# controller.net
KiCad netlist of a schematic drawn in EAGLE
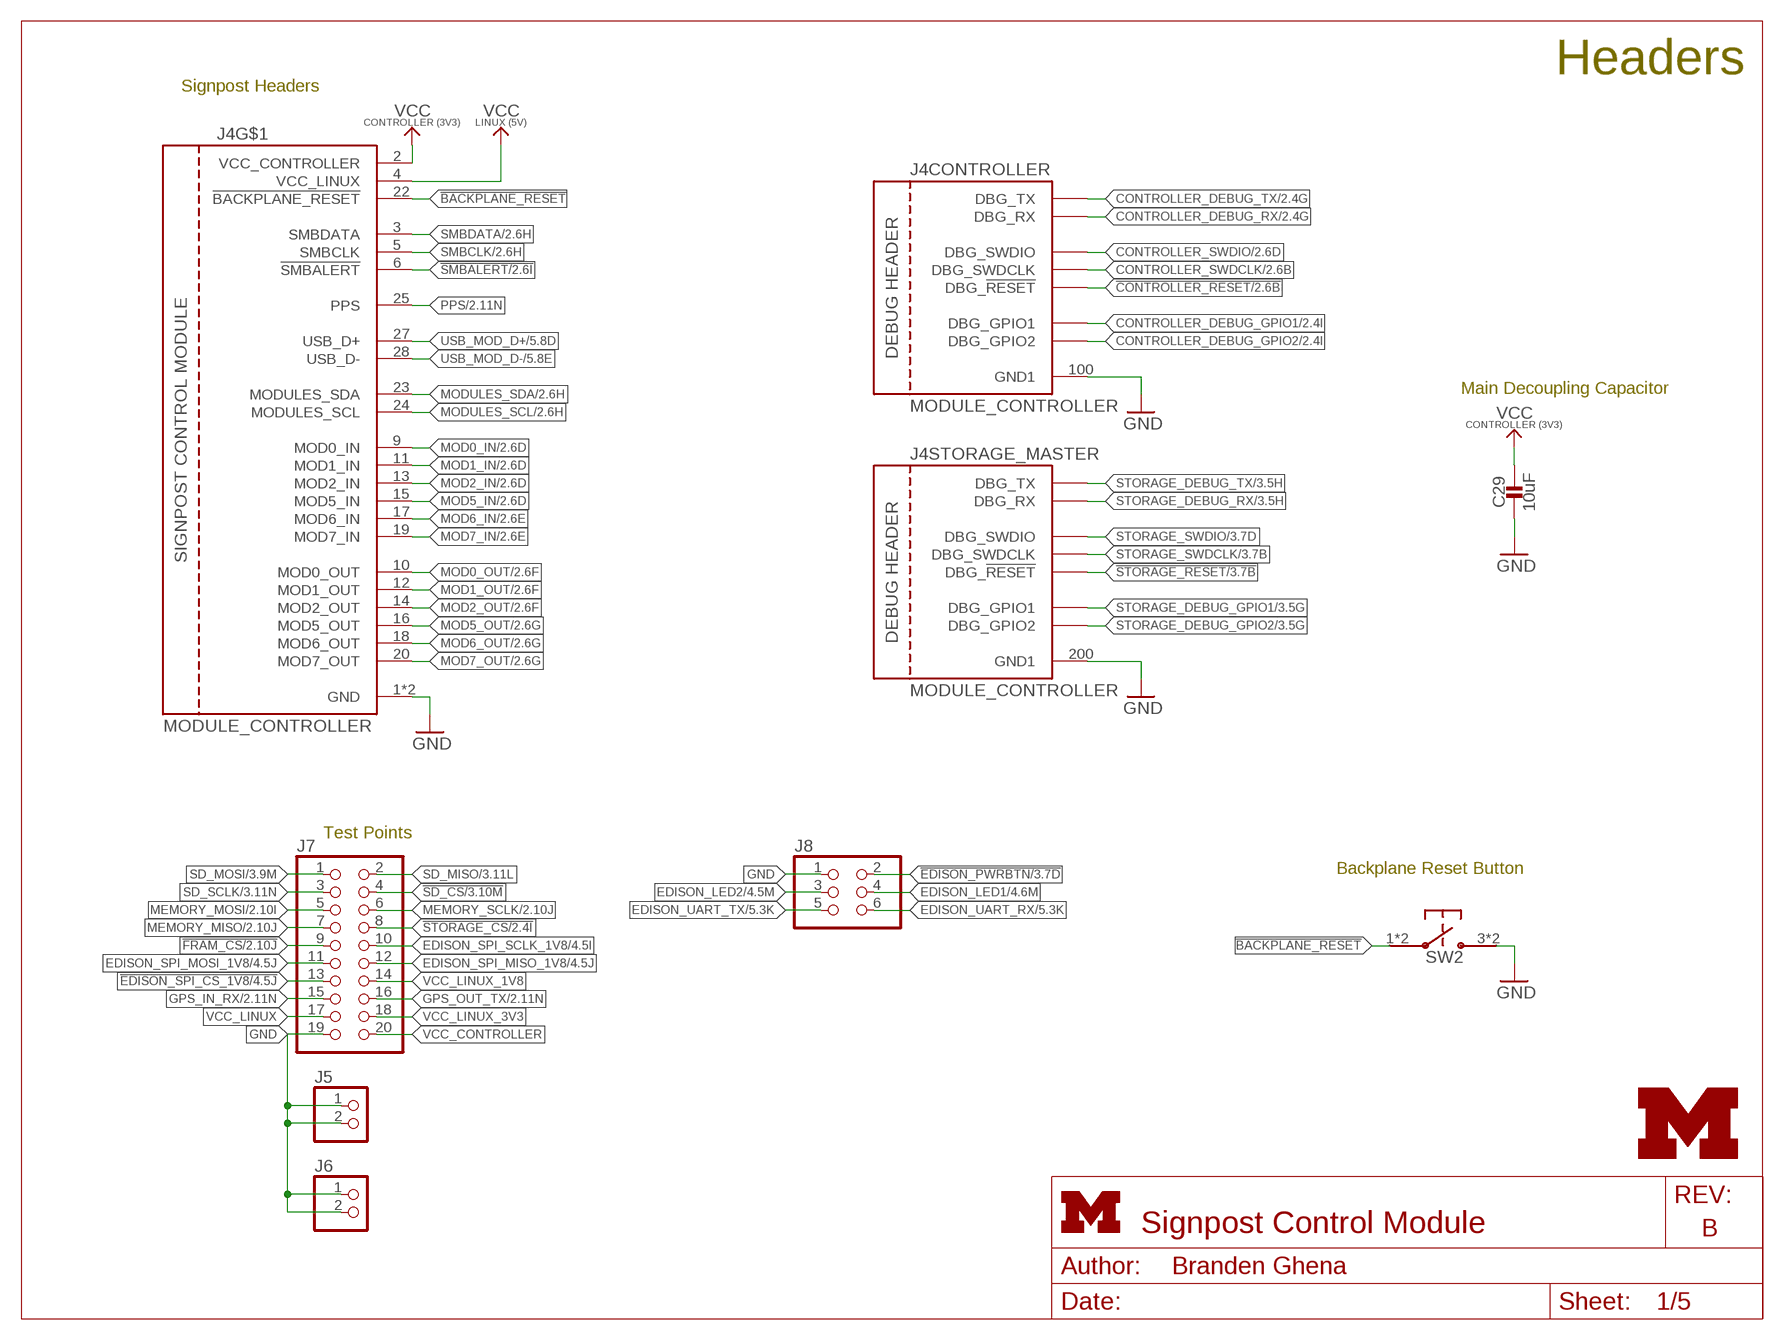
[diagram p0: schematic, sheet 1]
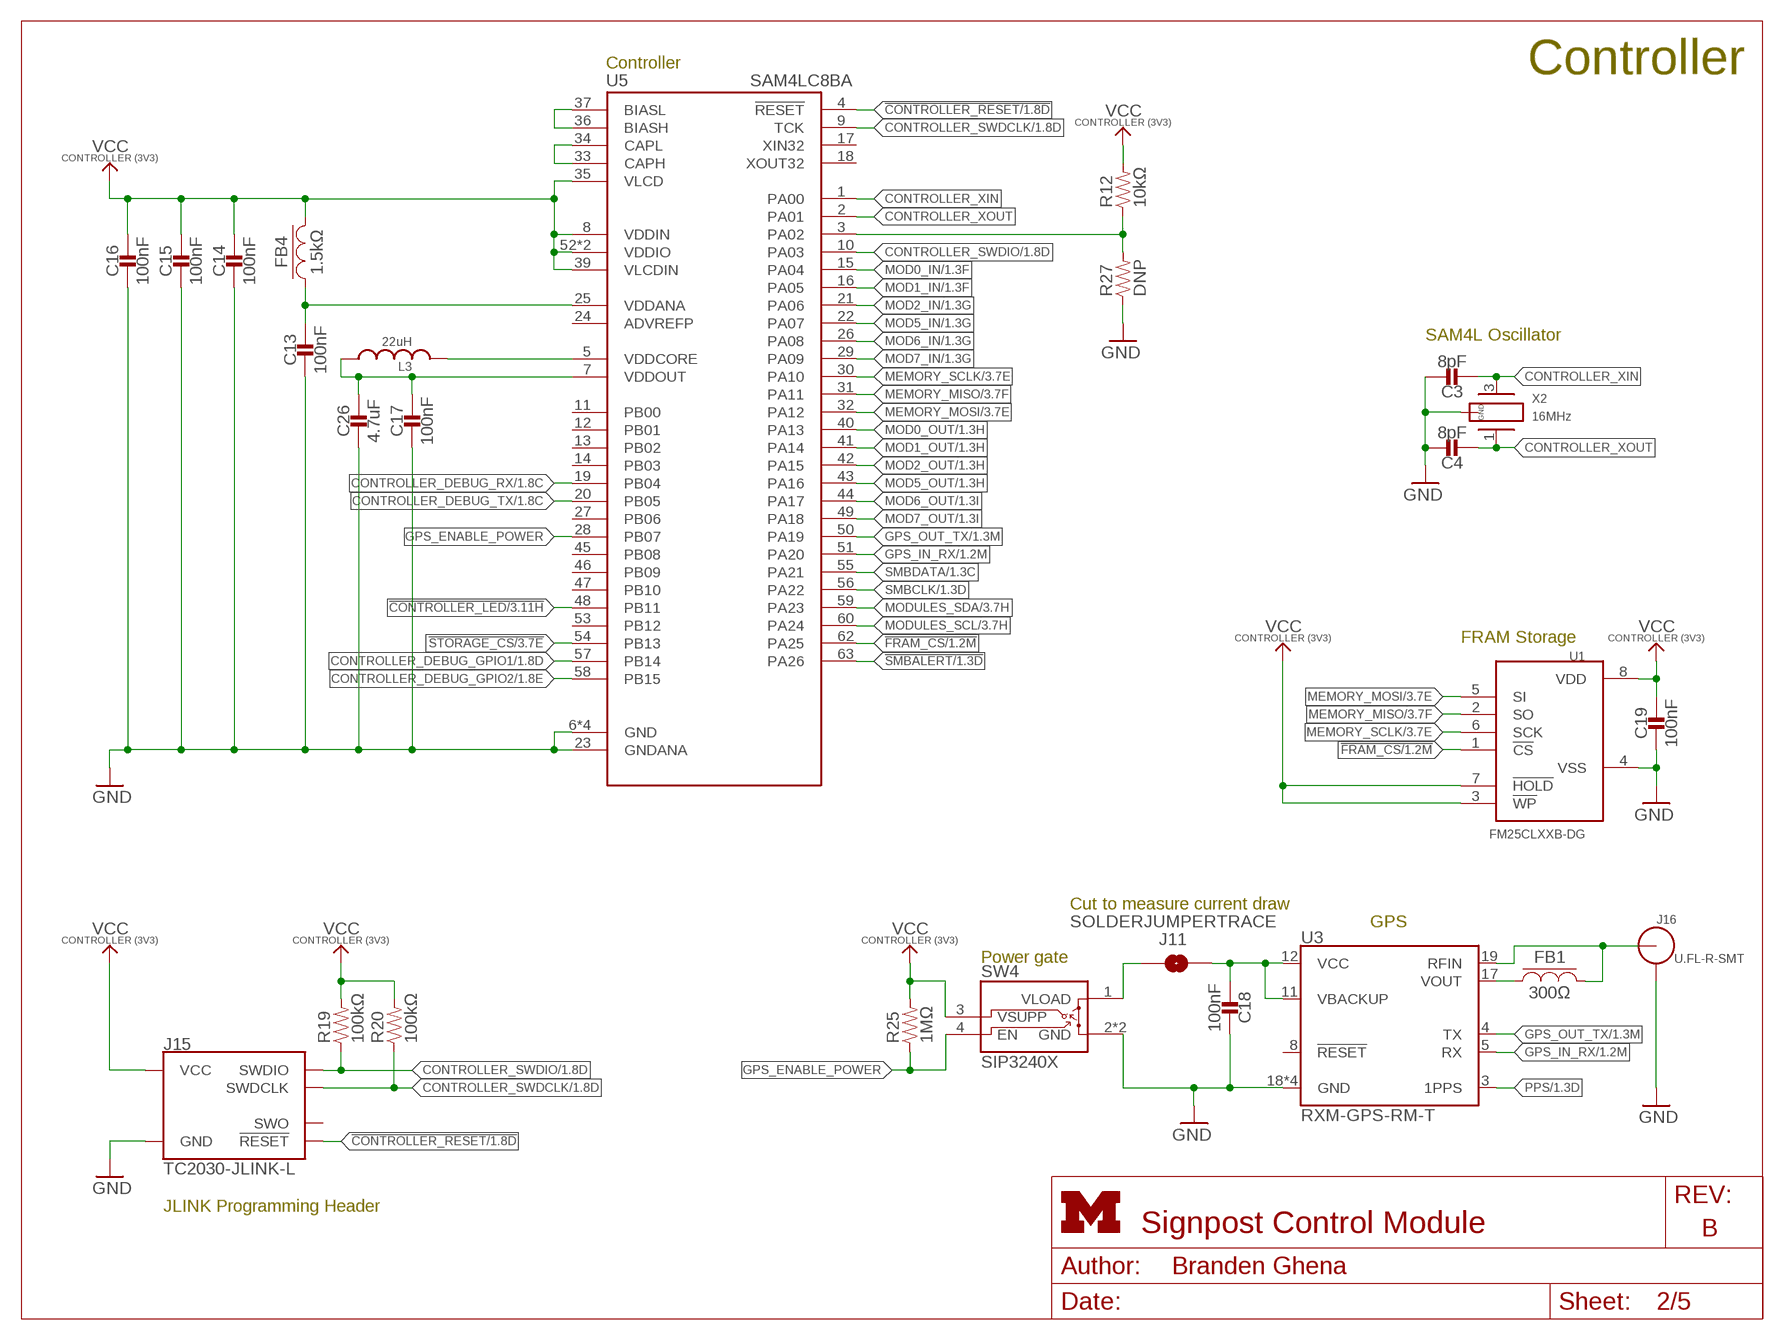
[diagram p1: schematic, sheet 2]
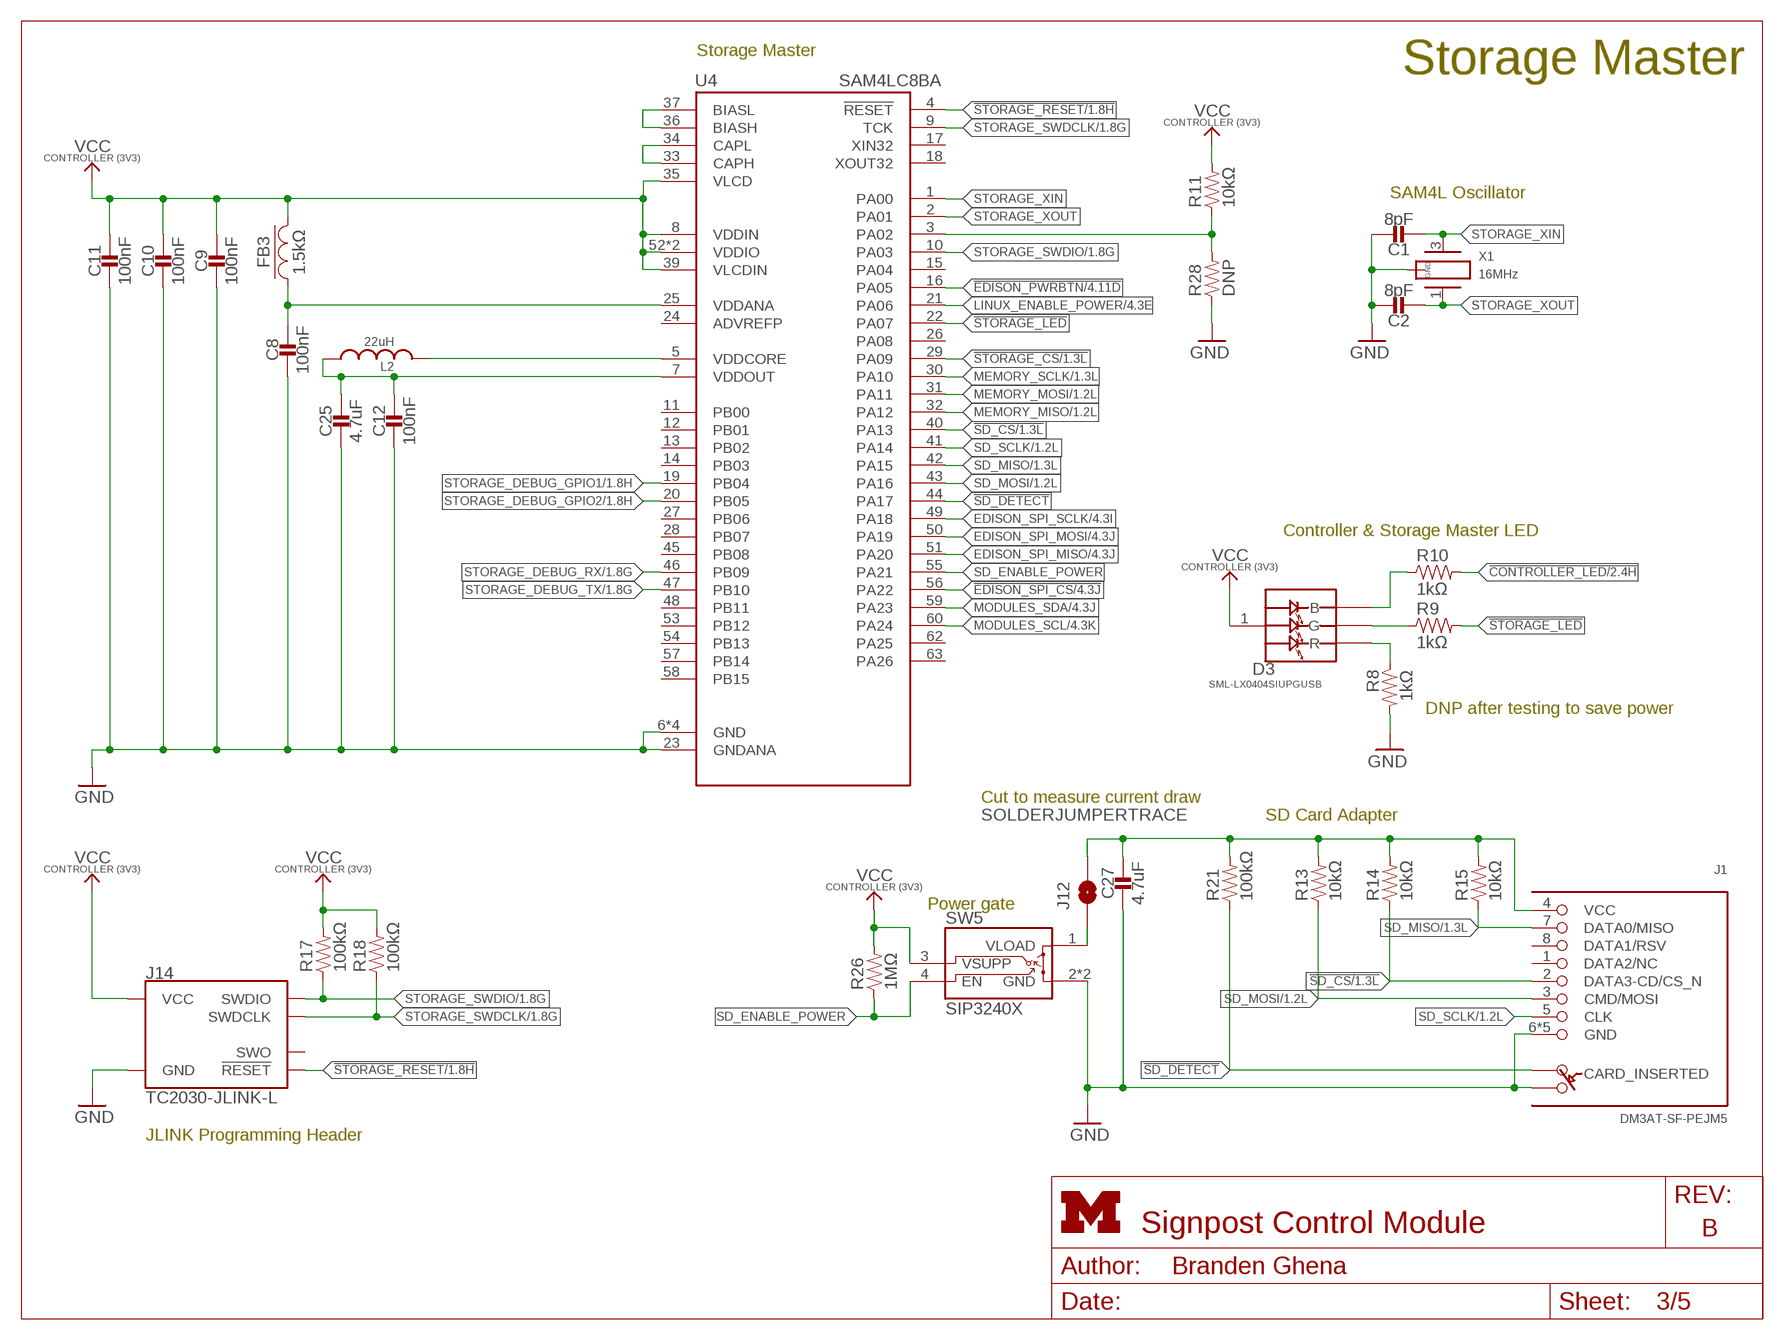
[diagram p2: schematic, sheet 3]
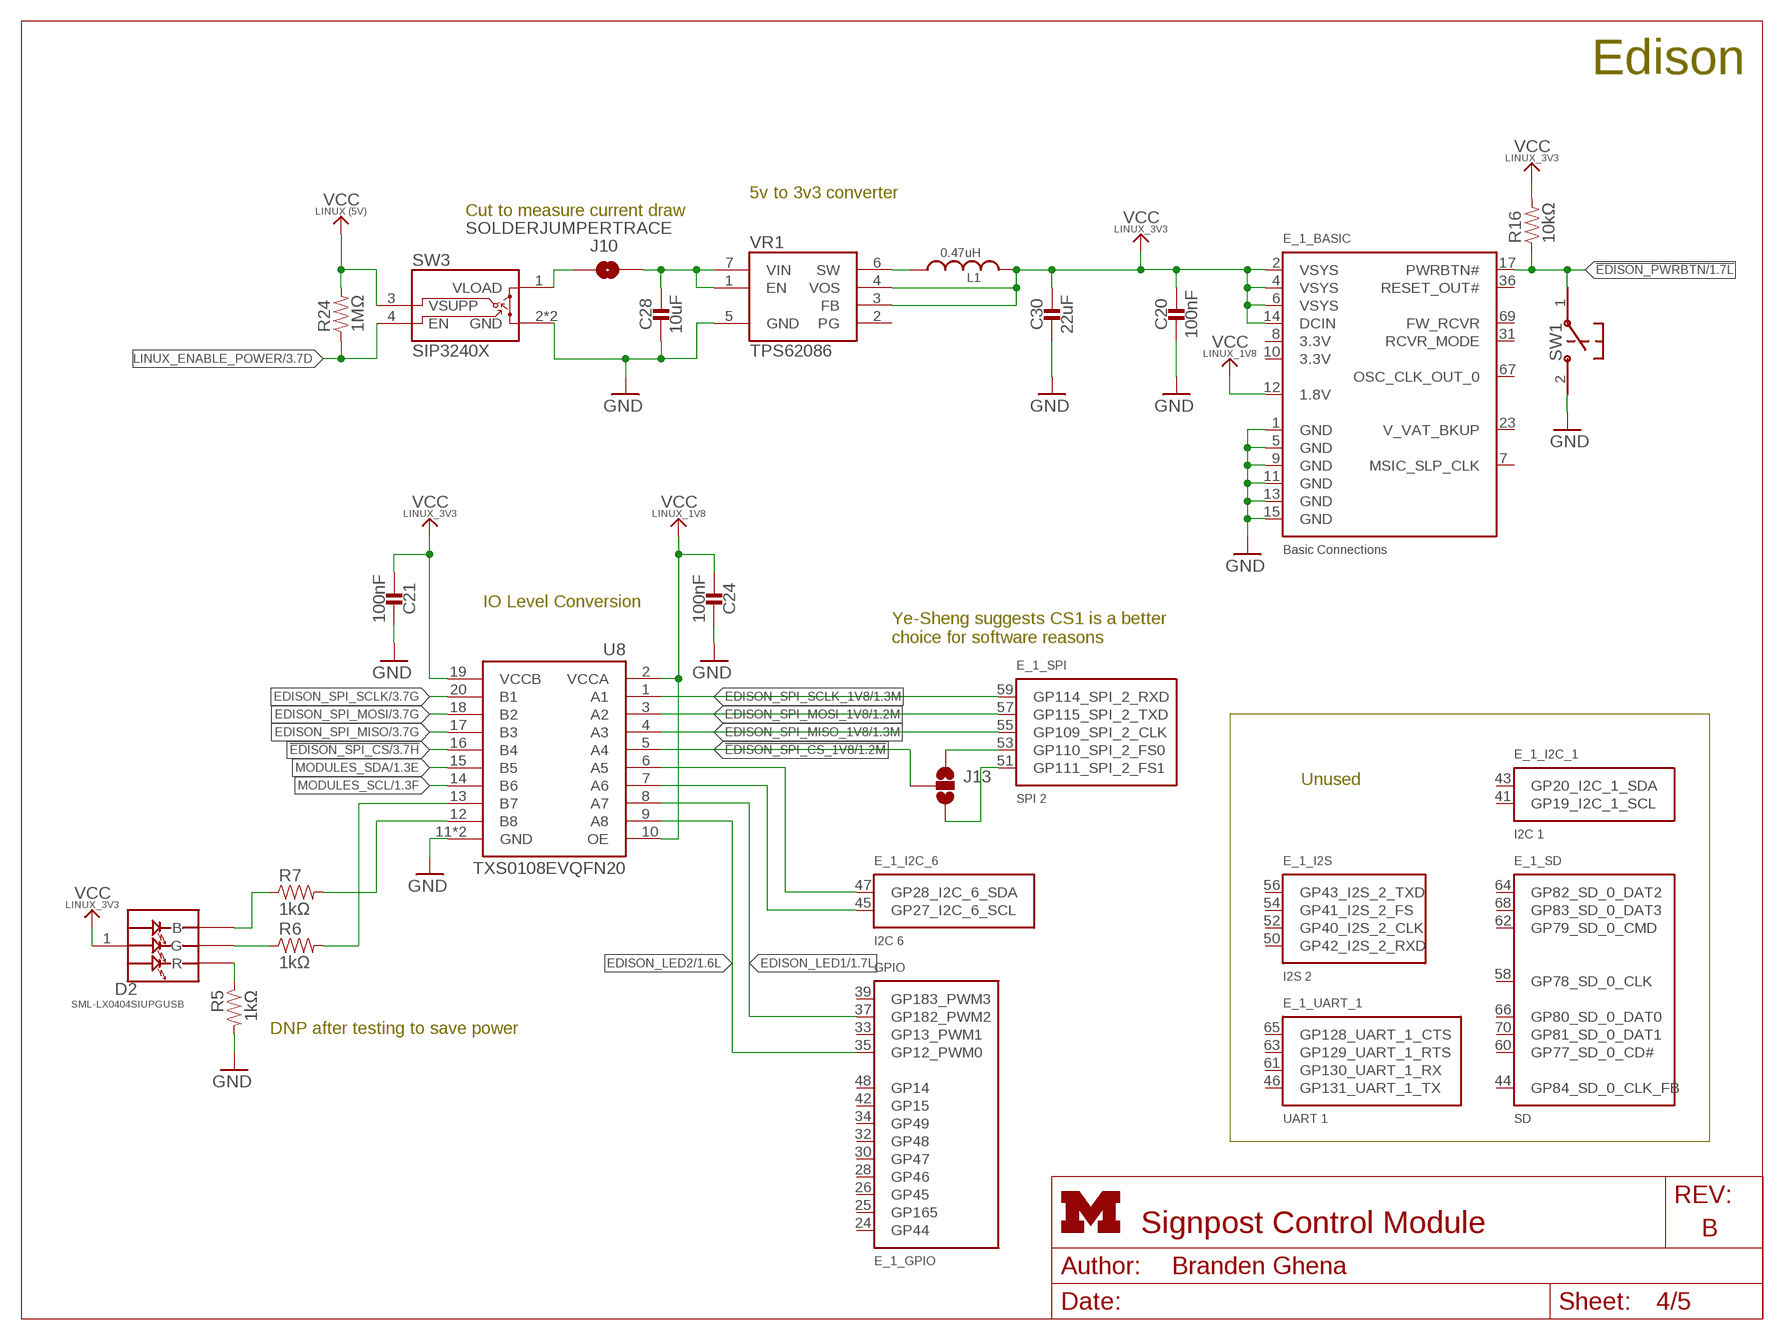
[diagram p3: schematic, sheet 4]
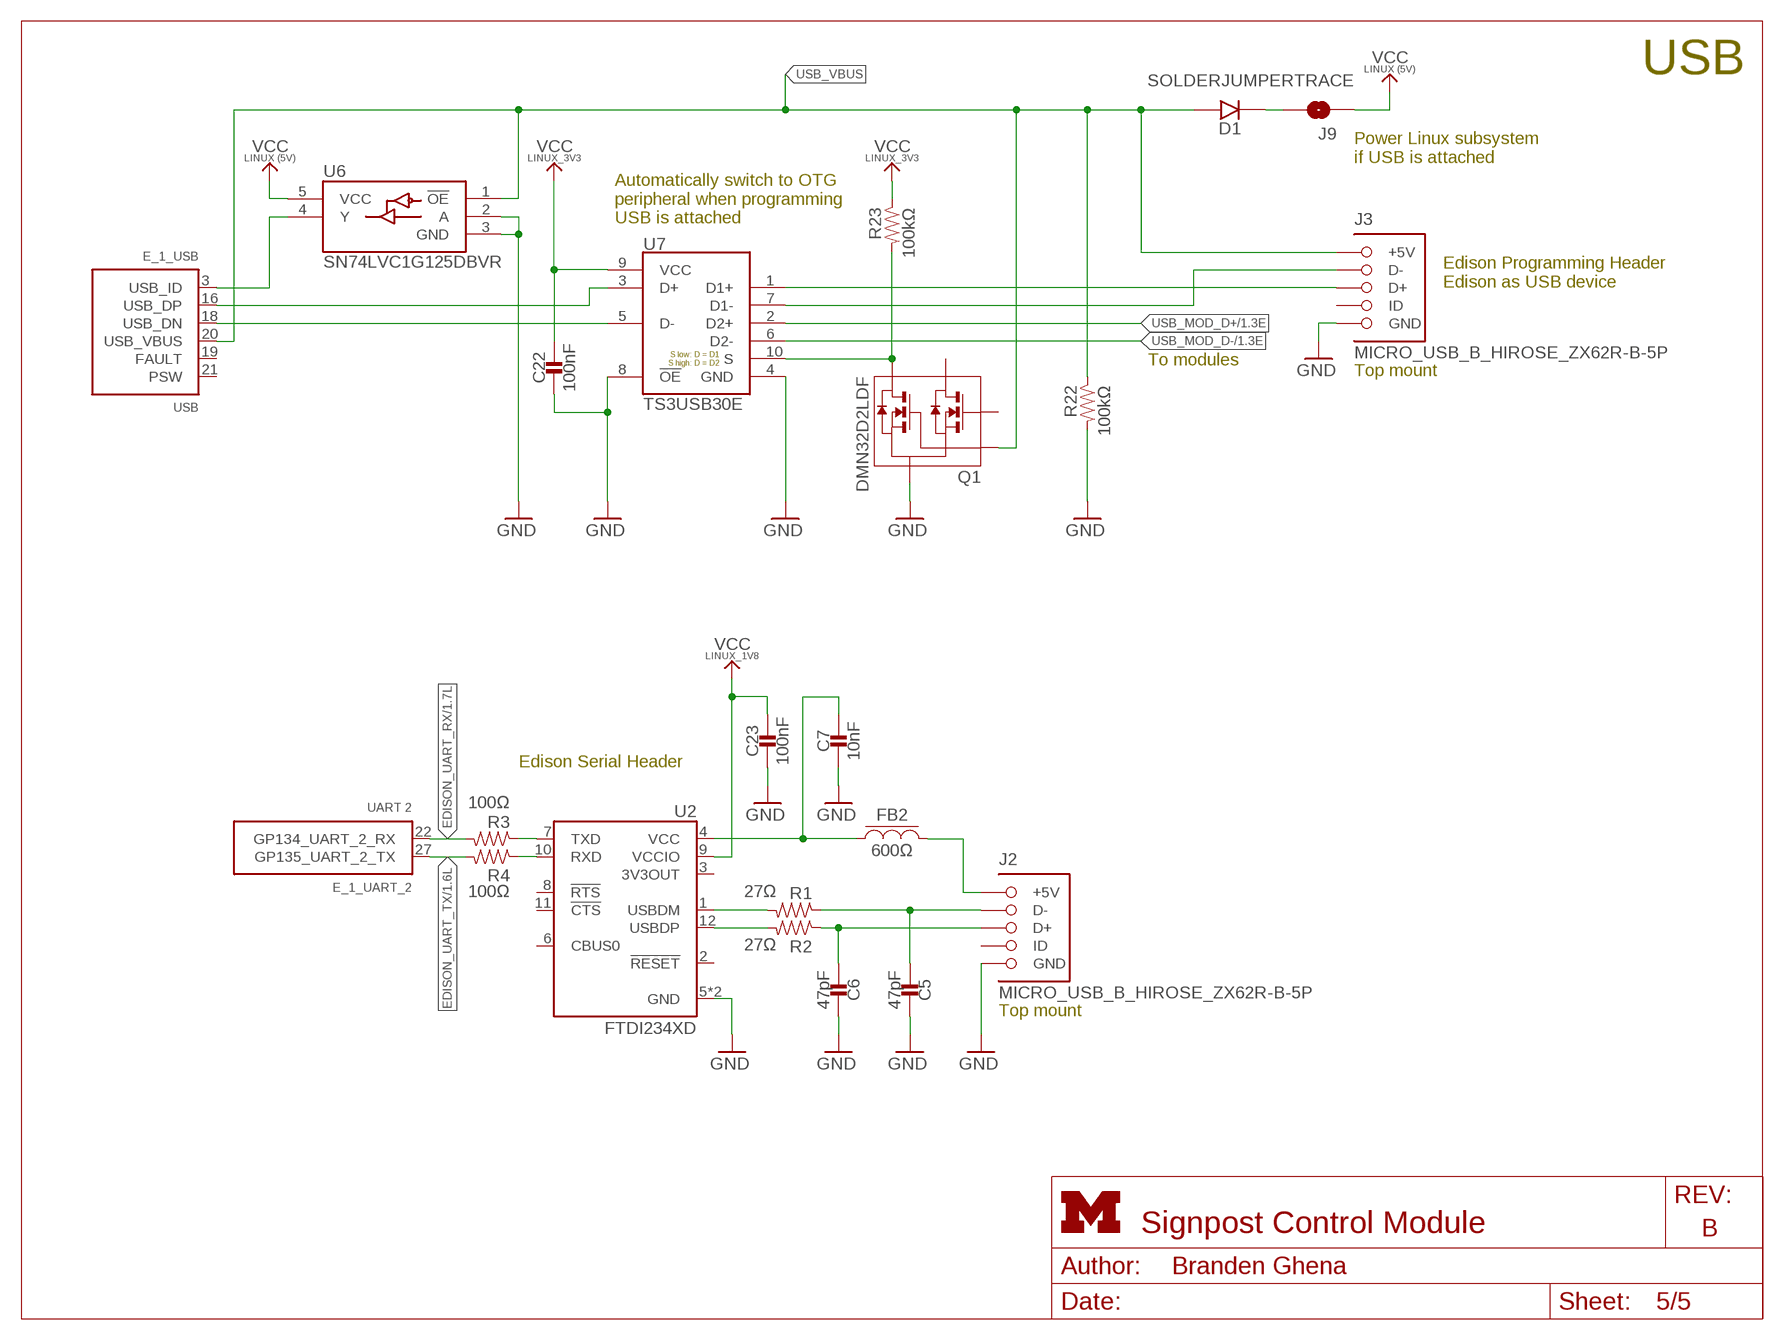
[diagram p4: schematic, sheet 5]

(export (version "E")
  (design (tool "Eeschema 10.0.6"))
  (components
    (comp (ref "C29")
      (value "10uF")
      (footprint "eagle-import:0402_CAP")
      (libsource (lib "eagle-import") (part "CAPACITOR0402_CAP"))
    )
    (comp (ref "J4")
      (value "MODULE_CONTROLLER")
      (footprint "eagle-import:MODULE_CONTROLLER")
      (libsource (lib "eagle-import") (part "MODULE_CONTROLLER"))
    )
    (comp (ref "J5")
      (value "PINHD-1X2")
      (footprint "eagle-import:1X02")
      (libsource (lib "eagle-import") (part "PINHD-1X2"))
    )
    (comp (ref "J6")
      (value "PINHD-1X2")
      (footprint "eagle-import:1X02")
      (libsource (lib "eagle-import") (part "PINHD-1X2"))
    )
    (comp (ref "J7")
      (value "PINHD-2X10")
      (footprint "eagle-import:2X10")
      (libsource (lib "eagle-import") (part "PINHD-2X10"))
    )
    (comp (ref "J8")
      (value "PINHD-2X3")
      (footprint "eagle-import:2X03")
      (libsource (lib "eagle-import") (part "PINHD-2X3"))
    )
    (comp (ref "LOGO1")
      (value "UMICH_SOLID_MEDIUM")
      (footprint "eagle-import:UMICH_SOLID_200MIL")
      (libsource (lib "eagle-import") (part "UMICH_SOLID_MEDIUM"))
    )
    (comp (ref "SW2")
      (value "PTS810SJ")
      (footprint "eagle-import:PTS810SJ")
      (libsource (lib "eagle-import") (part "PTS810SJ"))
    )
    (comp (ref "C1")
      (value "8pF")
      (footprint "eagle-import:0402_CAP")
      (libsource (lib "eagle-import") (part "CAPACITOR0402_CAP"))
    )
    (comp (ref "C2")
      (value "8pF")
      (footprint "eagle-import:0402_CAP")
      (libsource (lib "eagle-import") (part "CAPACITOR0402_CAP"))
    )
    (comp (ref "C8")
      (value "100nF")
      (footprint "eagle-import:0402_CAP")
      (libsource (lib "eagle-import") (part "CAPACITOR0402_CAP"))
    )
    (comp (ref "C9")
      (value "100nF")
      (footprint "eagle-import:0402_CAP")
      (libsource (lib "eagle-import") (part "CAPACITOR0402_CAP"))
    )
    (comp (ref "C10")
      (value "100nF")
      (footprint "eagle-import:0402_CAP")
      (libsource (lib "eagle-import") (part "CAPACITOR0402_CAP"))
    )
    (comp (ref "C11")
      (value "100nF")
      (footprint "eagle-import:0402_CAP")
      (libsource (lib "eagle-import") (part "CAPACITOR0402_CAP"))
    )
    (comp (ref "C12")
      (value "100nF")
      (footprint "eagle-import:0402_CAP")
      (libsource (lib "eagle-import") (part "CAPACITOR0402_CAP"))
    )
    (comp (ref "C25")
      (value "4.7uF")
      (footprint "eagle-import:0402_CAP")
      (libsource (lib "eagle-import") (part "CAPACITOR0402_CAP"))
    )
    (comp (ref "C27")
      (value "4.7uF")
      (footprint "eagle-import:0402_CAP")
      (libsource (lib "eagle-import") (part "CAPACITOR0402_CAP"))
    )
    (comp (ref "D3")
      (value "SML-LX0404SIUPGUSB")
      (footprint "eagle-import:1MM_SQ_4PAD")
      (libsource (lib "eagle-import") (part "SML-LX0404SIUPGUSB"))
    )
    (comp (ref "FB3")
      (value "1.5kΩ")
      (footprint "eagle-import:0402_CAP")
      (libsource (lib "eagle-import") (part "FERRITE_BEAD0402"))
    )
    (comp (ref "J1")
      (value "DM3AT-SF-PEJM5")
      (footprint "eagle-import:DM3AT-SF-PEJM5")
      (libsource (lib "eagle-import") (part "DM3AT-SF-PEJM5"))
    )
    (comp (ref "J12")
      (value "SOLDERJUMPERTRACE")
      (footprint "eagle-import:SJ_2S-TRACE")
      (libsource (lib "eagle-import") (part "SOLDERJUMPERTRACE"))
    )
    (comp (ref "J14")
      (value "TC2030-JLINK-L")
      (footprint "eagle-import:TC2030-IDC")
      (libsource (lib "eagle-import") (part "TC2030-JLINK-L"))
    )
    (comp (ref "L2")
      (value "22uH")
      (footprint "eagle-import:1212")
      (libsource (lib "eagle-import") (part "LHQ3NP"))
    )
    (comp (ref "R8")
      (value "1kΩ")
      (footprint "eagle-import:0402_RES")
      (libsource (lib "eagle-import") (part "RESISTOR0402_RES"))
    )
    (comp (ref "R9")
      (value "1kΩ")
      (footprint "eagle-import:0402_RES")
      (libsource (lib "eagle-import") (part "RESISTOR0402_RES"))
    )
    (comp (ref "R10")
      (value "1kΩ")
      (footprint "eagle-import:0402_RES")
      (libsource (lib "eagle-import") (part "RESISTOR0402_RES"))
    )
    (comp (ref "R11")
      (value "10kΩ")
      (footprint "eagle-import:0402_RES")
      (libsource (lib "eagle-import") (part "RESISTOR0402_RES"))
    )
    (comp (ref "R13")
      (value "10kΩ")
      (footprint "eagle-import:0402_RES")
      (libsource (lib "eagle-import") (part "RESISTOR0402_RES"))
    )
    (comp (ref "R14")
      (value "10kΩ")
      (footprint "eagle-import:0402_RES")
      (libsource (lib "eagle-import") (part "RESISTOR0402_RES"))
    )
    (comp (ref "R15")
      (value "10kΩ")
      (footprint "eagle-import:0402_RES")
      (libsource (lib "eagle-import") (part "RESISTOR0402_RES"))
    )
    (comp (ref "R17")
      (value "100kΩ")
      (footprint "eagle-import:0402_RES")
      (libsource (lib "eagle-import") (part "RESISTOR0402_RES"))
    )
    (comp (ref "R18")
      (value "100kΩ")
      (footprint "eagle-import:0402_RES")
      (libsource (lib "eagle-import") (part "RESISTOR0402_RES"))
    )
    (comp (ref "R21")
      (value "100kΩ")
      (footprint "eagle-import:0402_RES")
      (libsource (lib "eagle-import") (part "RESISTOR0402_RES"))
    )
    (comp (ref "R26")
      (value "1MΩ")
      (footprint "eagle-import:0402_RES")
      (libsource (lib "eagle-import") (part "RESISTOR0402_RES"))
    )
    (comp (ref "R28")
      (value "DNP")
      (footprint "eagle-import:0402_RES")
      (libsource (lib "eagle-import") (part "RESISTOR0402_RES"))
    )
    (comp (ref "SW5")
      (value "SIP3240X")
      (footprint "eagle-import:TDFN4")
      (libsource (lib "eagle-import") (part "SIP3240X"))
    )
    (comp (ref "U4")
      (value "SAM4LC8BA")
      (footprint "eagle-import:QFN-64-9MM")
      (libsource (lib "eagle-import") (part "SAM4LC8BA"))
    )
    (comp (ref "X1")
      (value "16MHz")
      (footprint "eagle-import:FHXXX")
      (libsource (lib "eagle-import") (part "FH1600015"))
    )
    (comp (ref "C20")
      (value "100nF")
      (footprint "eagle-import:0402_CAP")
      (libsource (lib "eagle-import") (part "CAPACITOR0402_CAP"))
    )
    (comp (ref "C21")
      (value "100nF")
      (footprint "eagle-import:0402_CAP")
      (libsource (lib "eagle-import") (part "CAPACITOR0402_CAP"))
    )
    (comp (ref "C24")
      (value "100nF")
      (footprint "eagle-import:0402_CAP")
      (libsource (lib "eagle-import") (part "CAPACITOR0402_CAP"))
    )
    (comp (ref "C28")
      (value "10uF")
      (footprint "eagle-import:0805_CAP")
      (libsource (lib "eagle-import") (part "CAPACITOR0805_CAP"))
    )
    (comp (ref "C30")
      (value "22uF")
      (footprint "eagle-import:0805_CAP")
      (libsource (lib "eagle-import") (part "CAPACITOR0805_CAP"))
    )
    (comp (ref "D2")
      (value "SML-LX0404SIUPGUSB")
      (footprint "eagle-import:1MM_SQ_4PAD")
      (libsource (lib "eagle-import") (part "SML-LX0404SIUPGUSB"))
    )
    (comp (ref "E_1")
      (value "EDISON_CONNECTOR_SEGMENTED")
      (footprint "eagle-import:EDISON_DAUGHTER")
      (fields (field (name "MOUSER") "798-DF40HC3070DS4V51") (field (name "AMAZON") "B00PTVSS4A"))
      (libsource (lib "eagle-import") (part "EDISON_CONNECTOR_SEGMENTED"))
    )
    (comp (ref "J10")
      (value "SOLDERJUMPERTRACE")
      (footprint "eagle-import:SJ_2S-TRACE")
      (libsource (lib "eagle-import") (part "SOLDERJUMPERTRACE"))
    )
    (comp (ref "J13")
      (value "SOLDERJUMPER_2WAYPASTE2&3")
      (footprint "eagle-import:SJ_3_PASTE2&3")
      (libsource (lib "eagle-import") (part "SOLDERJUMPER_2WAYPASTE2&3"))
    )
    (comp (ref "L1")
      (value "0.47uH")
      (footprint "eagle-import:DFE322512C")
      (libsource (lib "eagle-import") (part "INDUCTORDFE322512C"))
    )
    (comp (ref "R5")
      (value "1kΩ")
      (footprint "eagle-import:0402_RES")
      (libsource (lib "eagle-import") (part "RESISTOR0402_RES"))
    )
    (comp (ref "R6")
      (value "1kΩ")
      (footprint "eagle-import:0402_RES")
      (libsource (lib "eagle-import") (part "RESISTOR0402_RES"))
    )
    (comp (ref "R7")
      (value "1kΩ")
      (footprint "eagle-import:0402_RES")
      (libsource (lib "eagle-import") (part "RESISTOR0402_RES"))
    )
    (comp (ref "R16")
      (value "10kΩ")
      (footprint "eagle-import:0402_RES")
      (libsource (lib "eagle-import") (part "RESISTOR0402_RES"))
    )
    (comp (ref "R24")
      (value "1MΩ")
      (footprint "eagle-import:0402_RES")
      (libsource (lib "eagle-import") (part "RESISTOR0402_RES"))
    )
    (comp (ref "SW1")
      (value "B3U-1000P")
      (footprint "eagle-import:B3U-1000P")
      (libsource (lib "eagle-import") (part "B3U-1000P"))
    )
    (comp (ref "SW3")
      (value "SIP3240X")
      (footprint "eagle-import:TDFN4")
      (libsource (lib "eagle-import") (part "SIP3240X"))
    )
    (comp (ref "U8")
      (value "TXS0108EVQFN20")
      (footprint "eagle-import:R-PVQFN-N20")
      (libsource (lib "eagle-import") (part "TXS0108EVQFN20"))
    )
    (comp (ref "VR1")
      (value "TPS62086")
      (footprint "eagle-import:RLT0007A")
      (libsource (lib "eagle-import") (part "TPS62086"))
    )
    (comp (ref "C3")
      (value "8pF")
      (footprint "eagle-import:0402_CAP")
      (libsource (lib "eagle-import") (part "CAPACITOR0402_CAP"))
    )
    (comp (ref "C4")
      (value "8pF")
      (footprint "eagle-import:0402_CAP")
      (libsource (lib "eagle-import") (part "CAPACITOR0402_CAP"))
    )
    (comp (ref "C13")
      (value "100nF")
      (footprint "eagle-import:0402_CAP")
      (libsource (lib "eagle-import") (part "CAPACITOR0402_CAP"))
    )
    (comp (ref "C14")
      (value "100nF")
      (footprint "eagle-import:0402_CAP")
      (libsource (lib "eagle-import") (part "CAPACITOR0402_CAP"))
    )
    (comp (ref "C15")
      (value "100nF")
      (footprint "eagle-import:0402_CAP")
      (libsource (lib "eagle-import") (part "CAPACITOR0402_CAP"))
    )
    (comp (ref "C16")
      (value "100nF")
      (footprint "eagle-import:0402_CAP")
      (libsource (lib "eagle-import") (part "CAPACITOR0402_CAP"))
    )
    (comp (ref "C17")
      (value "100nF")
      (footprint "eagle-import:0402_CAP")
      (libsource (lib "eagle-import") (part "CAPACITOR0402_CAP"))
    )
    (comp (ref "C18")
      (value "100nF")
      (footprint "eagle-import:0402_CAP")
      (libsource (lib "eagle-import") (part "CAPACITOR0402_CAP"))
    )
    (comp (ref "C19")
      (value "100nF")
      (footprint "eagle-import:0402_CAP")
      (libsource (lib "eagle-import") (part "CAPACITOR0402_CAP"))
    )
    (comp (ref "C26")
      (value "4.7uF")
      (footprint "eagle-import:0402_CAP")
      (libsource (lib "eagle-import") (part "CAPACITOR0402_CAP"))
    )
    (comp (ref "FB1")
      (value "300Ω")
      (footprint "eagle-import:0402_CAP")
      (libsource (lib "eagle-import") (part "FERRITE_BEAD0402"))
    )
    (comp (ref "FB4")
      (value "1.5kΩ")
      (footprint "eagle-import:0402_CAP")
      (libsource (lib "eagle-import") (part "FERRITE_BEAD0402"))
    )
    (comp (ref "J11")
      (value "SOLDERJUMPERTRACE")
      (footprint "eagle-import:SJ_2S-TRACE")
      (libsource (lib "eagle-import") (part "SOLDERJUMPERTRACE"))
    )
    (comp (ref "J15")
      (value "TC2030-JLINK-L")
      (footprint "eagle-import:TC2030-IDC")
      (libsource (lib "eagle-import") (part "TC2030-JLINK-L"))
    )
    (comp (ref "J16")
      (value "U.FL-R-SMT")
      (footprint "eagle-import:U.FL_SMT")
      (libsource (lib "eagle-import") (part "U.FL-R-SMT"))
    )
    (comp (ref "L3")
      (value "22uH")
      (footprint "eagle-import:1212")
      (libsource (lib "eagle-import") (part "LHQ3NP"))
    )
    (comp (ref "R12")
      (value "10kΩ")
      (footprint "eagle-import:0402_RES")
      (libsource (lib "eagle-import") (part "RESISTOR0402_RES"))
    )
    (comp (ref "R19")
      (value "100kΩ")
      (footprint "eagle-import:0402_RES")
      (libsource (lib "eagle-import") (part "RESISTOR0402_RES"))
    )
    (comp (ref "R20")
      (value "100kΩ")
      (footprint "eagle-import:0402_RES")
      (libsource (lib "eagle-import") (part "RESISTOR0402_RES"))
    )
    (comp (ref "R25")
      (value "1MΩ")
      (footprint "eagle-import:0402_RES")
      (libsource (lib "eagle-import") (part "RESISTOR0402_RES"))
    )
    (comp (ref "R27")
      (value "DNP")
      (footprint "eagle-import:0402_RES")
      (libsource (lib "eagle-import") (part "RESISTOR0402_RES"))
    )
    (comp (ref "SW4")
      (value "SIP3240X")
      (footprint "eagle-import:TDFN4")
      (libsource (lib "eagle-import") (part "SIP3240X"))
    )
    (comp (ref "U1")
      (value "FM25CLXXB-DG")
      (footprint "eagle-import:TDFN-8")
      (libsource (lib "eagle-import") (part "FM25CLXXB-DG"))
    )
    (comp (ref "U3")
      (value "RXM-GPS-RM-T")
      (footprint "eagle-import:RXM-GPS-RM-T")
      (libsource (lib "eagle-import") (part "RXM-GPS-RM-T"))
    )
    (comp (ref "U5")
      (value "SAM4LC8BA")
      (footprint "eagle-import:QFN-64-9MM")
      (libsource (lib "eagle-import") (part "SAM4LC8BA"))
    )
    (comp (ref "X2")
      (value "16MHz")
      (footprint "eagle-import:FHXXX")
      (libsource (lib "eagle-import") (part "FH1600015"))
    )
    (comp (ref "C5")
      (value "47pF")
      (footprint "eagle-import:0402_CAP")
      (libsource (lib "eagle-import") (part "CAPACITOR0402_CAP"))
    )
    (comp (ref "C6")
      (value "47pF")
      (footprint "eagle-import:0402_CAP")
      (libsource (lib "eagle-import") (part "CAPACITOR0402_CAP"))
    )
    (comp (ref "C7")
      (value "10nF")
      (footprint "eagle-import:0402_CAP")
      (libsource (lib "eagle-import") (part "CAPACITOR0402_CAP"))
    )
    (comp (ref "C22")
      (value "100nF")
      (footprint "eagle-import:0402_CAP")
      (libsource (lib "eagle-import") (part "CAPACITOR0402_CAP"))
    )
    (comp (ref "C23")
      (value "100nF")
      (footprint "eagle-import:0402_CAP")
      (libsource (lib "eagle-import") (part "CAPACITOR0402_CAP"))
    )
    (comp (ref "D1")
      (value "DIODE")
      (footprint "eagle-import:0805_DIODE")
      (libsource (lib "eagle-import") (part "DIODE"))
    )
    (comp (ref "FB2")
      (value "600Ω")
      (footprint "eagle-import:0805_CAP")
      (libsource (lib "eagle-import") (part "FERRITE_BEAD0805"))
    )
    (comp (ref "J2")
      (value "MICRO_USB_B_HIROSE_ZX62R-B-5P")
      (footprint "eagle-import:USB_MICRO_B-HIROSE-ZX62R-B-5P")
      (fields (field (name "DIGIKEY") "H125274CT-ND"))
      (libsource (lib "eagle-import") (part "MICRO_USB_B_HIROSE_ZX62R-B-5P"))
    )
    (comp (ref "J3")
      (value "MICRO_USB_B_HIROSE_ZX62R-B-5P")
      (footprint "eagle-import:USB_MICRO_B-HIROSE-ZX62R-B-5P")
      (fields (field (name "DIGIKEY") "H125274CT-ND"))
      (libsource (lib "eagle-import") (part "MICRO_USB_B_HIROSE_ZX62R-B-5P"))
    )
    (comp (ref "J9")
      (value "SOLDERJUMPERTRACE")
      (footprint "eagle-import:SJ_2S-TRACE")
      (libsource (lib "eagle-import") (part "SOLDERJUMPERTRACE"))
    )
    (comp (ref "Q1")
      (value "DMN32D2LDF")
      (footprint "eagle-import:SOT353")
      (libsource (lib "eagle-import") (part "DMN32D2LDF"))
    )
    (comp (ref "R1")
      (value "27Ω")
      (footprint "eagle-import:0402_RES")
      (libsource (lib "eagle-import") (part "RESISTOR0402_RES"))
    )
    (comp (ref "R2")
      (value "27Ω")
      (footprint "eagle-import:0402_RES")
      (libsource (lib "eagle-import") (part "RESISTOR0402_RES"))
    )
    (comp (ref "R3")
      (value "100Ω")
      (footprint "eagle-import:0402_RES")
      (libsource (lib "eagle-import") (part "RESISTOR0402_RES"))
    )
    (comp (ref "R4")
      (value "100Ω")
      (footprint "eagle-import:0402_RES")
      (libsource (lib "eagle-import") (part "RESISTOR0402_RES"))
    )
    (comp (ref "R22")
      (value "100kΩ")
      (footprint "eagle-import:0402_RES")
      (libsource (lib "eagle-import") (part "RESISTOR0402_RES"))
    )
    (comp (ref "R23")
      (value "100kΩ")
      (footprint "eagle-import:0402_RES")
      (libsource (lib "eagle-import") (part "RESISTOR0402_RES"))
    )
    (comp (ref "U2")
      (value "FTDI234XD")
      (footprint "eagle-import:DFN-12_3MM")
      (libsource (lib "eagle-import") (part "FTDI234XD"))
    )
    (comp (ref "U6")
      (value "SN74LVC1G125DBVR")
      (footprint "eagle-import:SOT-23-5")
      (libsource (lib "eagle-import") (part "SN74LVC1G125DBVR"))
    )
    (comp (ref "U7")
      (value "TS3USB30E")
      (footprint "eagle-import:UQFN-10")
      (libsource (lib "eagle-import") (part "TS3USB30E"))
    )
  )
  (nets
    (net (code "1") (name "CONTROLLER_DEBUG_GPIO1") (class "Default")
      (node (ref "J4") (pin "101") (pinfunction "DBG_GPIO1_101") (pintype "bidirectional"))
      (node (ref "U5") (pin "57") (pinfunction "PB14_57") (pintype "bidirectional"))
    )
    (net (code "2") (name "CONTROLLER_DEBUG_GPIO2") (class "Default")
      (node (ref "J4") (pin "104") (pinfunction "DBG_GPIO2_104") (pintype "bidirectional"))
      (node (ref "U5") (pin "58") (pinfunction "PB15_58") (pintype "bidirectional"))
    )
    (net (code "3") (name "CONTROLLER_DEBUG_RX") (class "Default")
      (node (ref "J4") (pin "103") (pinfunction "DBG_RX_103") (pintype "bidirectional"))
      (node (ref "U5") (pin "19") (pinfunction "PB04_19") (pintype "bidirectional"))
    )
    (net (code "4") (name "CONTROLLER_DEBUG_TX") (class "Default")
      (node (ref "J4") (pin "102") (pinfunction "DBG_TX_102") (pintype "bidirectional"))
      (node (ref "U5") (pin "20") (pinfunction "PB05_20") (pintype "bidirectional"))
    )
    (net (code "5") (name "CONTROLLER_SWDCLK") (class "Default")
      (node (ref "J15") (pin "4") (pinfunction "SWDCLK_4") (pintype "bidirectional"))
      (node (ref "J4") (pin "106") (pinfunction "DBG_SWDCLK_106") (pintype "bidirectional"))
      (node (ref "R20") (pin "1") (pinfunction "1_1") (pintype "passive"))
      (node (ref "U5") (pin "9") (pinfunction "TCK_9") (pintype "bidirectional"))
    )
    (net (code "6") (name "CONTROLLER_SWDIO") (class "Default")
      (node (ref "J15") (pin "2") (pinfunction "SWDIO_2") (pintype "bidirectional"))
      (node (ref "J4") (pin "107") (pinfunction "DBG_SWDIO_107") (pintype "bidirectional"))
      (node (ref "R19") (pin "1") (pinfunction "1_1") (pintype "passive"))
      (node (ref "U5") (pin "10") (pinfunction "PA03_10") (pintype "bidirectional"))
    )
    (net (code "7") (name "CONTROLLER_XIN") (class "Default")
      (node (ref "C3") (pin "1") (pinfunction "1_1") (pintype "bidirectional"))
      (node (ref "U5") (pin "1") (pinfunction "PA00_1") (pintype "bidirectional"))
      (node (ref "X2") (pin "3") (pinfunction "2_3") (pintype "bidirectional"))
    )
    (net (code "8") (name "CONTROLLER_XOUT") (class "Default")
      (node (ref "C4") (pin "1") (pinfunction "1_1") (pintype "bidirectional"))
      (node (ref "U5") (pin "2") (pinfunction "PA01_2") (pintype "bidirectional"))
      (node (ref "X2") (pin "1") (pinfunction "1_1") (pintype "bidirectional"))
    )
    (net (code "9") (name "EDISON_LED1") (class "Default")
      (node (ref "E_1") (pin "37") (pinfunction "GP182_PWM2_37") (pintype "bidirectional"))
      (node (ref "J8") (pin "4") (pinfunction "4_4") (pintype "passive"))
      (node (ref "U8") (pin "8") (pinfunction "A7_8") (pintype "bidirectional"))
    )
    (net (code "10") (name "EDISON_LED2") (class "Default")
      (node (ref "E_1") (pin "35") (pinfunction "GP12_PWM0_35") (pintype "bidirectional"))
      (node (ref "J8") (pin "3") (pinfunction "3_3") (pintype "passive"))
      (node (ref "U8") (pin "9") (pinfunction "A8_9") (pintype "bidirectional"))
    )
    (net (code "11") (name "EDISON_SPI_MISO") (class "Default")
      (node (ref "U4") (pin "51") (pinfunction "PA20_51") (pintype "bidirectional"))
      (node (ref "U8") (pin "17") (pinfunction "B3_17") (pintype "bidirectional"))
    )
    (net (code "12") (name "EDISON_SPI_MISO_1V8") (class "Default")
      (node (ref "E_1") (pin "55") (pinfunction "GP109_SPI_2_CLK_55") (pintype "bidirectional"))
      (node (ref "J7") (pin "12") (pinfunction "12_12") (pintype "passive"))
      (node (ref "U8") (pin "4") (pinfunction "A3_4") (pintype "bidirectional"))
    )
    (net (code "13") (name "EDISON_SPI_MOSI") (class "Default")
      (node (ref "U4") (pin "50") (pinfunction "PA19_50") (pintype "bidirectional"))
      (node (ref "U8") (pin "18") (pinfunction "B2_18") (pintype "bidirectional"))
    )
    (net (code "14") (name "EDISON_SPI_MOSI_1V8") (class "Default")
      (node (ref "E_1") (pin "57") (pinfunction "GP115_SPI_2_TXD_57") (pintype "bidirectional"))
      (node (ref "J7") (pin "11") (pinfunction "11_11") (pintype "passive"))
      (node (ref "U8") (pin "3") (pinfunction "A2_3") (pintype "bidirectional"))
    )
    (net (code "15") (name "EDISON_SPI_SCLK") (class "Default")
      (node (ref "U4") (pin "49") (pinfunction "PA18_49") (pintype "bidirectional"))
      (node (ref "U8") (pin "20") (pinfunction "B1_20") (pintype "bidirectional"))
    )
    (net (code "16") (name "EDISON_SPI_SCLK_1V8") (class "Default")
      (node (ref "E_1") (pin "59") (pinfunction "GP114_SPI_2_RXD_59") (pintype "bidirectional"))
      (node (ref "J7") (pin "10") (pinfunction "10_10") (pintype "passive"))
      (node (ref "U8") (pin "1") (pinfunction "A1_1") (pintype "bidirectional"))
    )
    (net (code "17") (name "EDISON_UART_RX") (class "Default")
      (node (ref "E_1") (pin "22") (pinfunction "GP134_UART_2_RX_22") (pintype "bidirectional"))
      (node (ref "J8") (pin "6") (pinfunction "6_6") (pintype "passive"))
      (node (ref "R3") (pin "2") (pinfunction "2_2") (pintype "passive"))
    )
    (net (code "18") (name "EDISON_UART_TX") (class "Default")
      (node (ref "E_1") (pin "27") (pinfunction "GP135_UART_2_TX_27") (pintype "bidirectional"))
      (node (ref "J8") (pin "5") (pinfunction "5_5") (pintype "passive"))
      (node (ref "R4") (pin "2") (pinfunction "2_2") (pintype "passive"))
    )
    (net (code "19") (name "GND") (class "Default")
      (node (ref "C1") (pin "2") (pinfunction "2_2") (pintype "bidirectional"))
      (node (ref "C10") (pin "2") (pinfunction "2_2") (pintype "bidirectional"))
      (node (ref "C11") (pin "2") (pinfunction "2_2") (pintype "bidirectional"))
      (node (ref "C12") (pin "2") (pinfunction "2_2") (pintype "bidirectional"))
      (node (ref "C13") (pin "2") (pinfunction "2_2") (pintype "bidirectional"))
      (node (ref "C14") (pin "2") (pinfunction "2_2") (pintype "bidirectional"))
      (node (ref "C15") (pin "2") (pinfunction "2_2") (pintype "bidirectional"))
      (node (ref "C16") (pin "2") (pinfunction "2_2") (pintype "bidirectional"))
      (node (ref "C17") (pin "2") (pinfunction "2_2") (pintype "bidirectional"))
      (node (ref "C18") (pin "2") (pinfunction "2_2") (pintype "bidirectional"))
      (node (ref "C19") (pin "2") (pinfunction "2_2") (pintype "bidirectional"))
      (node (ref "C2") (pin "2") (pinfunction "2_2") (pintype "bidirectional"))
      (node (ref "C20") (pin "2") (pinfunction "2_2") (pintype "bidirectional"))
      (node (ref "C21") (pin "1") (pinfunction "1_1") (pintype "bidirectional"))
      (node (ref "C22") (pin "2") (pinfunction "2_2") (pintype "bidirectional"))
      (node (ref "C23") (pin "2") (pinfunction "2_2") (pintype "bidirectional"))
      (node (ref "C24") (pin "1") (pinfunction "1_1") (pintype "bidirectional"))
      (node (ref "C25") (pin "2") (pinfunction "2_2") (pintype "bidirectional"))
      (node (ref "C26") (pin "2") (pinfunction "2_2") (pintype "bidirectional"))
      (node (ref "C27") (pin "2") (pinfunction "2_2") (pintype "bidirectional"))
      (node (ref "C28") (pin "P$2") (pinfunction "2_P$2") (pintype "bidirectional"))
      (node (ref "C29") (pin "2") (pinfunction "2_2") (pintype "bidirectional"))
      (node (ref "C3") (pin "2") (pinfunction "2_2") (pintype "bidirectional"))
      (node (ref "C30") (pin "P$2") (pinfunction "2_P$2") (pintype "bidirectional"))
      (node (ref "C4") (pin "2") (pinfunction "2_2") (pintype "bidirectional"))
      (node (ref "C5") (pin "2") (pinfunction "2_2") (pintype "bidirectional"))
      (node (ref "C6") (pin "2") (pinfunction "2_2") (pintype "bidirectional"))
      (node (ref "C7") (pin "2") (pinfunction "2_2") (pintype "bidirectional"))
      (node (ref "C8") (pin "2") (pinfunction "2_2") (pintype "bidirectional"))
      (node (ref "C9") (pin "2") (pinfunction "2_2") (pintype "bidirectional"))
      (node (ref "E_1") (pin "1") (pinfunction "GND_1") (pintype "bidirectional"))
      (node (ref "E_1") (pin "11") (pinfunction "GND_11") (pintype "bidirectional"))
      (node (ref "E_1") (pin "13") (pinfunction "GND_13") (pintype "bidirectional"))
      (node (ref "E_1") (pin "15") (pinfunction "GND_15") (pintype "bidirectional"))
      (node (ref "E_1") (pin "5") (pinfunction "GND_5") (pintype "bidirectional"))
      (node (ref "E_1") (pin "9") (pinfunction "GND_9") (pintype "bidirectional"))
      (node (ref "J1") (pin "6") (pinfunction "GND_6") (pintype "bidirectional"))
      (node (ref "J1") (pin "B") (pinfunction "B_B") (pintype "bidirectional"))
      (node (ref "J1") (pin "MOUNT0") (pinfunction "GND_MOUNT0") (pintype "bidirectional"))
      (node (ref "J1") (pin "MOUNT1") (pinfunction "GND_MOUNT1") (pintype "bidirectional"))
      (node (ref "J1") (pin "MOUNT2") (pinfunction "GND_MOUNT2") (pintype "bidirectional"))
      (node (ref "J1") (pin "MOUNT3") (pinfunction "GND_MOUNT3") (pintype "bidirectional"))
      (node (ref "J14") (pin "5") (pinfunction "GND_5") (pintype "bidirectional"))
      (node (ref "J15") (pin "5") (pinfunction "GND_5") (pintype "bidirectional"))
      (node (ref "J16") (pin "GND1") (pinfunction "P$2_GND1") (pintype "bidirectional"))
      (node (ref "J16") (pin "GND2") (pinfunction "P$2_GND2") (pintype "bidirectional"))
      (node (ref "J2") (pin "5") (pinfunction "GND_5") (pintype "bidirectional"))
      (node (ref "J3") (pin "5") (pinfunction "GND_5") (pintype "bidirectional"))
      (node (ref "J4") (pin "1") (pinfunction "GND_1") (pintype "bidirectional"))
      (node (ref "J4") (pin "100") (pinfunction "GND1_100") (pintype "bidirectional"))
      (node (ref "J4") (pin "200") (pinfunction "GND1_200") (pintype "bidirectional"))
      (node (ref "J4") (pin "21") (pinfunction "GND_21") (pintype "bidirectional"))
      (node (ref "J5") (pin "1") (pinfunction "1_1") (pintype "passive"))
      (node (ref "J5") (pin "2") (pinfunction "2_2") (pintype "passive"))
      (node (ref "J6") (pin "1") (pinfunction "1_1") (pintype "passive"))
      (node (ref "J6") (pin "2") (pinfunction "2_2") (pintype "passive"))
      (node (ref "J7") (pin "19") (pinfunction "19_19") (pintype "passive"))
      (node (ref "J8") (pin "1") (pinfunction "1_1") (pintype "passive"))
      (node (ref "Q1") (pin "S") (pinfunction "S_S") (pintype "bidirectional"))
      (node (ref "R22") (pin "2") (pinfunction "2_2") (pintype "passive"))
      (node (ref "R27") (pin "1") (pinfunction "1_1") (pintype "passive"))
      (node (ref "R28") (pin "1") (pinfunction "1_1") (pintype "passive"))
      (node (ref "R5") (pin "2") (pinfunction "2_2") (pintype "passive"))
      (node (ref "R8") (pin "2") (pinfunction "2_2") (pintype "passive"))
      (node (ref "SW1") (pin "2") (pinfunction "P$2_2") (pintype "passive"))
      (node (ref "SW2") (pin "3") (pinfunction "P$2_3") (pintype "passive"))
      (node (ref "SW2") (pin "4") (pinfunction "P$2_4") (pintype "passive"))
      (node (ref "SW3") (pin "2") (pinfunction "GND_2") (pintype "bidirectional"))
      (node (ref "SW3") (pin "PAD") (pinfunction "GND_PAD") (pintype "bidirectional"))
      (node (ref "SW4") (pin "2") (pinfunction "GND_2") (pintype "bidirectional"))
      (node (ref "SW4") (pin "PAD") (pinfunction "GND_PAD") (pintype "bidirectional"))
      (node (ref "SW5") (pin "2") (pinfunction "GND_2") (pintype "bidirectional"))
      (node (ref "SW5") (pin "PAD") (pinfunction "GND_PAD") (pintype "bidirectional"))
      (node (ref "U1") (pin "4") (pinfunction "VSS_4") (pintype "bidirectional"))
      (node (ref "U2") (pin "13") (pinfunction "GND_13") (pintype "bidirectional"))
      (node (ref "U2") (pin "5") (pinfunction "GND_5") (pintype "bidirectional"))
      (node (ref "U3") (pin "18") (pinfunction "GND_18") (pintype "bidirectional"))
      (node (ref "U3") (pin "20") (pinfunction "GND_20") (pintype "bidirectional"))
      (node (ref "U3") (pin "21") (pinfunction "GND_21") (pintype "bidirectional"))
      (node (ref "U3") (pin "22") (pinfunction "GND_22") (pintype "bidirectional"))
      (node (ref "U4") (pin "23") (pinfunction "GNDANA_23") (pintype "power_in"))
      (node (ref "U4") (pin "38") (pinfunction "GND_38") (pintype "power_in"))
      (node (ref "U4") (pin "6") (pinfunction "GND_6") (pintype "power_in"))
      (node (ref "U4") (pin "64") (pinfunction "GND_64") (pintype "power_in"))
      (node (ref "U4") (pin "GND") (pinfunction "GND_GND") (pintype "power_in"))
      (node (ref "U5") (pin "23") (pinfunction "GNDANA_23") (pintype "power_in"))
      (node (ref "U5") (pin "38") (pinfunction "GND_38") (pintype "power_in"))
      (node (ref "U5") (pin "6") (pinfunction "GND_6") (pintype "power_in"))
      (node (ref "U5") (pin "64") (pinfunction "GND_64") (pintype "power_in"))
      (node (ref "U5") (pin "GND") (pinfunction "GND_GND") (pintype "power_in"))
      (node (ref "U6") (pin "2") (pinfunction "A_2") (pintype "bidirectional"))
      (node (ref "U6") (pin "3") (pinfunction "GND_3") (pintype "power_in"))
      (node (ref "U7") (pin "4") (pinfunction "GND_4") (pintype "bidirectional"))
      (node (ref "U7") (pin "8") (pinfunction "~{OE}_8") (pintype "bidirectional"))
      (node (ref "U8") (pin "11") (pinfunction "GND_11") (pintype "bidirectional"))
      (node (ref "U8") (pin "THERMAL") (pinfunction "GND_THERMAL") (pintype "bidirectional"))
      (node (ref "VR1") (pin "5") (pinfunction "GND_5") (pintype "bidirectional"))
      (node (ref "X1") (pin "2") (pinfunction "GND_2") (pintype "bidirectional"))
      (node (ref "X1") (pin "4") (pinfunction "GND_4") (pintype "bidirectional"))
      (node (ref "X2") (pin "2") (pinfunction "GND_2") (pintype "bidirectional"))
      (node (ref "X2") (pin "4") (pinfunction "GND_4") (pintype "bidirectional"))
    )
    (net (code "20") (name "GPS_ENABLE_POWER") (class "Default")
      (node (ref "R25") (pin "1") (pinfunction "1_1") (pintype "passive"))
      (node (ref "SW4") (pin "4") (pinfunction "EN_4") (pintype "bidirectional"))
      (node (ref "U5") (pin "28") (pinfunction "PB07_28") (pintype "bidirectional"))
    )
    (net (code "21") (name "GPS_IN_RX") (class "Default")
      (node (ref "J7") (pin "15") (pinfunction "15_15") (pintype "passive"))
      (node (ref "U3") (pin "5") (pinfunction "RX_5") (pintype "bidirectional"))
      (node (ref "U5") (pin "51") (pinfunction "PA20_51") (pintype "bidirectional"))
    )
    (net (code "22") (name "GPS_OUT_TX") (class "Default")
      (node (ref "J7") (pin "16") (pinfunction "16_16") (pintype "passive"))
      (node (ref "U3") (pin "4") (pinfunction "TX_4") (pintype "bidirectional"))
      (node (ref "U5") (pin "50") (pinfunction "PA19_50") (pintype "bidirectional"))
    )
    (net (code "23") (name "LINUX_ENABLE_POWER") (class "Default")
      (node (ref "R24") (pin "1") (pinfunction "1_1") (pintype "passive"))
      (node (ref "SW3") (pin "4") (pinfunction "EN_4") (pintype "bidirectional"))
      (node (ref "U4") (pin "21") (pinfunction "PA06_21") (pintype "bidirectional"))
    )
    (net (code "24") (name "MEMORY_MISO") (class "Default")
      (node (ref "J7") (pin "7") (pinfunction "7_7") (pintype "passive"))
      (node (ref "U1") (pin "2") (pinfunction "SO_2") (pintype "bidirectional"))
      (node (ref "U4") (pin "32") (pinfunction "PA12_32") (pintype "bidirectional"))
      (node (ref "U5") (pin "31") (pinfunction "PA11_31") (pintype "bidirectional"))
    )
    (net (code "25") (name "MEMORY_MOSI") (class "Default")
      (node (ref "J7") (pin "5") (pinfunction "5_5") (pintype "passive"))
      (node (ref "U1") (pin "5") (pinfunction "SI_5") (pintype "bidirectional"))
      (node (ref "U4") (pin "31") (pinfunction "PA11_31") (pintype "bidirectional"))
      (node (ref "U5") (pin "32") (pinfunction "PA12_32") (pintype "bidirectional"))
    )
    (net (code "26") (name "MEMORY_SCLK") (class "Default")
      (node (ref "J7") (pin "6") (pinfunction "6_6") (pintype "passive"))
      (node (ref "U1") (pin "6") (pinfunction "SCK_6") (pintype "bidirectional"))
      (node (ref "U4") (pin "30") (pinfunction "PA10_30") (pintype "bidirectional"))
      (node (ref "U5") (pin "30") (pinfunction "PA10_30") (pintype "bidirectional"))
    )
    (net (code "27") (name "MOD0_IN") (class "Default")
      (node (ref "J4") (pin "9") (pinfunction "MOD0_IN_9") (pintype "bidirectional"))
      (node (ref "U5") (pin "15") (pinfunction "PA04_15") (pintype "bidirectional"))
    )
    (net (code "28") (name "MOD0_OUT") (class "Default")
      (node (ref "J4") (pin "10") (pinfunction "MOD0_OUT_10") (pintype "bidirectional"))
      (node (ref "U5") (pin "40") (pinfunction "PA13_40") (pintype "bidirectional"))
    )
    (net (code "29") (name "MOD1_IN") (class "Default")
      (node (ref "J4") (pin "11") (pinfunction "MOD1_IN_11") (pintype "bidirectional"))
      (node (ref "U5") (pin "16") (pinfunction "PA05_16") (pintype "bidirectional"))
    )
    (net (code "30") (name "MOD1_OUT") (class "Default")
      (node (ref "J4") (pin "12") (pinfunction "MOD1_OUT_12") (pintype "bidirectional"))
      (node (ref "U5") (pin "41") (pinfunction "PA14_41") (pintype "bidirectional"))
    )
    (net (code "31") (name "MOD2_IN") (class "Default")
      (node (ref "J4") (pin "13") (pinfunction "MOD2_IN_13") (pintype "bidirectional"))
      (node (ref "U5") (pin "21") (pinfunction "PA06_21") (pintype "bidirectional"))
    )
    (net (code "32") (name "MOD2_OUT") (class "Default")
      (node (ref "J4") (pin "14") (pinfunction "MOD2_OUT_14") (pintype "bidirectional"))
      (node (ref "U5") (pin "42") (pinfunction "PA15_42") (pintype "bidirectional"))
    )
    (net (code "33") (name "MOD5_IN") (class "Default")
      (node (ref "J4") (pin "15") (pinfunction "MOD5_IN_15") (pintype "bidirectional"))
      (node (ref "U5") (pin "22") (pinfunction "PA07_22") (pintype "bidirectional"))
    )
    (net (code "34") (name "MOD5_OUT") (class "Default")
      (node (ref "J4") (pin "16") (pinfunction "MOD5_OUT_16") (pintype "bidirectional"))
      (node (ref "U5") (pin "43") (pinfunction "PA16_43") (pintype "bidirectional"))
    )
    (net (code "35") (name "MOD6_IN") (class "Default")
      (node (ref "J4") (pin "17") (pinfunction "MOD6_IN_17") (pintype "bidirectional"))
      (node (ref "U5") (pin "26") (pinfunction "PA08_26") (pintype "bidirectional"))
    )
    (net (code "36") (name "MOD6_OUT") (class "Default")
      (node (ref "J4") (pin "18") (pinfunction "MOD6_OUT_18") (pintype "bidirectional"))
      (node (ref "U5") (pin "44") (pinfunction "PA17_44") (pintype "bidirectional"))
    )
    (net (code "37") (name "MOD7_IN") (class "Default")
      (node (ref "J4") (pin "19") (pinfunction "MOD7_IN_19") (pintype "bidirectional"))
      (node (ref "U5") (pin "29") (pinfunction "PA09_29") (pintype "bidirectional"))
    )
    (net (code "38") (name "MOD7_OUT") (class "Default")
      (node (ref "J4") (pin "20") (pinfunction "MOD7_OUT_20") (pintype "bidirectional"))
      (node (ref "U5") (pin "49") (pinfunction "PA18_49") (pintype "bidirectional"))
    )
    (net (code "39") (name "MODULES_SCL") (class "Default")
      (node (ref "J4") (pin "24") (pinfunction "MODULES_SCL_24") (pintype "bidirectional"))
      (node (ref "U4") (pin "60") (pinfunction "PA24_60") (pintype "bidirectional"))
      (node (ref "U5") (pin "60") (pinfunction "PA24_60") (pintype "bidirectional"))
      (node (ref "U8") (pin "14") (pinfunction "B6_14") (pintype "bidirectional"))
    )
    (net (code "40") (name "MODULES_SDA") (class "Default")
      (node (ref "J4") (pin "23") (pinfunction "MODULES_SDA_23") (pintype "bidirectional"))
      (node (ref "U4") (pin "59") (pinfunction "PA23_59") (pintype "bidirectional"))
      (node (ref "U5") (pin "59") (pinfunction "PA23_59") (pintype "bidirectional"))
      (node (ref "U8") (pin "15") (pinfunction "B5_15") (pintype "bidirectional"))
    )
    (net (code "41") (name "Net-(C28-1)") (class "Default")
      (node (ref "C28") (pin "P$1") (pinfunction "1_P$1") (pintype "bidirectional"))
      (node (ref "J10") (pin "2") (pinfunction "2_2") (pintype "passive"))
      (node (ref "VR1") (pin "1") (pinfunction "EN_1") (pintype "bidirectional"))
      (node (ref "VR1") (pin "7") (pinfunction "VIN_7") (pintype "bidirectional"))
    )
    (net (code "42") (name "Net-(D1-PadCATHODE)") (class "Default")
      (node (ref "D1") (pin "CATHODE") (pinfunction "CATHODE_CATHODE") (pintype "bidirectional"))
      (node (ref "J9") (pin "2") (pinfunction "2_2") (pintype "passive"))
    )
    (net (code "43") (name "Net-(D2-B)") (class "Default")
      (node (ref "D2") (pin "3") (pinfunction "B_3") (pintype "output"))
      (node (ref "R7") (pin "1") (pinfunction "1_1") (pintype "passive"))
    )
    (net (code "44") (name "Net-(D2-G)") (class "Default")
      (node (ref "D2") (pin "4") (pinfunction "G_4") (pintype "output"))
      (node (ref "R6") (pin "1") (pinfunction "1_1") (pintype "passive"))
    )
    (net (code "45") (name "Net-(D2-R)") (class "Default")
      (node (ref "D2") (pin "2") (pinfunction "R_2") (pintype "output"))
      (node (ref "R5") (pin "1") (pinfunction "1_1") (pintype "passive"))
    )
    (net (code "46") (name "Net-(D3-B)") (class "Default")
      (node (ref "D3") (pin "3") (pinfunction "B_3") (pintype "output"))
      (node (ref "R10") (pin "1") (pinfunction "1_1") (pintype "passive"))
    )
    (net (code "47") (name "Net-(D3-G)") (class "Default")
      (node (ref "D3") (pin "4") (pinfunction "G_4") (pintype "output"))
      (node (ref "R9") (pin "1") (pinfunction "1_1") (pintype "passive"))
    )
    (net (code "48") (name "Net-(D3-R)") (class "Default")
      (node (ref "D3") (pin "2") (pinfunction "R_2") (pintype "output"))
      (node (ref "R8") (pin "1") (pinfunction "1_1") (pintype "passive"))
    )
    (net (code "49") (name "Net-(E_1D-GP27_I2C_6_SCL)") (class "Default")
      (node (ref "E_1") (pin "45") (pinfunction "GP27_I2C_6_SCL_45") (pintype "bidirectional"))
      (node (ref "U8") (pin "7") (pinfunction "A6_7") (pintype "bidirectional"))
    )
    (net (code "50") (name "Net-(E_1D-GP28_I2C_6_SDA)") (class "Default")
      (node (ref "E_1") (pin "47") (pinfunction "GP28_I2C_6_SDA_47") (pintype "bidirectional"))
      (node (ref "U8") (pin "6") (pinfunction "A5_6") (pintype "bidirectional"))
    )
    (net (code "51") (name "Net-(E_1G-GP110_SPI_2_FS0)") (class "Default")
      (node (ref "E_1") (pin "53") (pinfunction "GP110_SPI_2_FS0_53") (pintype "bidirectional"))
      (node (ref "J13") (pin "1") (pinfunction "1_1") (pintype "passive"))
    )
    (net (code "52") (name "Net-(E_1G-GP111_SPI_2_FS1)") (class "Default")
      (node (ref "E_1") (pin "51") (pinfunction "GP111_SPI_2_FS1_51") (pintype "bidirectional"))
      (node (ref "J13") (pin "3") (pinfunction "3_3") (pintype "passive"))
    )
    (net (code "53") (name "Net-(E_1J-USB_DN)") (class "Default")
      (node (ref "E_1") (pin "18") (pinfunction "USB_DN_18") (pintype "bidirectional"))
      (node (ref "U7") (pin "5") (pinfunction "D-_5") (pintype "bidirectional"))
    )
    (net (code "54") (name "Net-(E_1J-USB_DP)") (class "Default")
      (node (ref "E_1") (pin "16") (pinfunction "USB_DP_16") (pintype "bidirectional"))
      (node (ref "U7") (pin "3") (pinfunction "D+_3") (pintype "bidirectional"))
    )
    (net (code "55") (name "Net-(E_1J-USB_ID)") (class "Default")
      (node (ref "E_1") (pin "3") (pinfunction "USB_ID_3") (pintype "bidirectional"))
      (node (ref "U6") (pin "4") (pinfunction "Y_4") (pintype "bidirectional"))
    )
    (net (code "56") (name "Net-(FB1-P$1)") (class "Default")
      (node (ref "FB1") (pin "1") (pinfunction "P$1_1") (pintype "bidirectional"))
      (node (ref "U3") (pin "17") (pinfunction "VOUT_17") (pintype "bidirectional"))
    )
    (net (code "57") (name "Net-(FB1-P$2)") (class "Default")
      (node (ref "FB1") (pin "2") (pinfunction "P$2_2") (pintype "bidirectional"))
      (node (ref "J16") (pin "SIG") (pinfunction "ANT_SIG") (pintype "bidirectional"))
      (node (ref "U3") (pin "19") (pinfunction "RFIN_19") (pintype "bidirectional"))
    )
    (net (code "58") (name "Net-(FB3-P$1)") (class "Default")
      (node (ref "C8") (pin "1") (pinfunction "1_1") (pintype "bidirectional"))
      (node (ref "FB3") (pin "1") (pinfunction "P$1_1") (pintype "bidirectional"))
      (node (ref "U4") (pin "25") (pinfunction "VDDANA_25") (pintype "power_in"))
    )
    (net (code "59") (name "Net-(FB4-P$1)") (class "Default")
      (node (ref "C13") (pin "1") (pinfunction "1_1") (pintype "bidirectional"))
      (node (ref "FB4") (pin "1") (pinfunction "P$1_1") (pintype "bidirectional"))
      (node (ref "U5") (pin "25") (pinfunction "VDDANA_25") (pintype "power_in"))
    )
    (net (code "60") (name "Net-(J1-VCC)") (class "Default")
      (node (ref "C27") (pin "1") (pinfunction "1_1") (pintype "bidirectional"))
      (node (ref "J1") (pin "4") (pinfunction "VCC_4") (pintype "bidirectional"))
      (node (ref "J12") (pin "2") (pinfunction "2_2") (pintype "passive"))
      (node (ref "R13") (pin "2") (pinfunction "2_2") (pintype "passive"))
      (node (ref "R14") (pin "2") (pinfunction "2_2") (pintype "passive"))
      (node (ref "R15") (pin "2") (pinfunction "2_2") (pintype "passive"))
      (node (ref "R21") (pin "2") (pinfunction "2_2") (pintype "passive"))
    )
    (net (code "61") (name "Net-(J2-+5V)") (class "Default")
      (node (ref "FB2") (pin "P$2") (pinfunction "P$2_P$2") (pintype "bidirectional"))
      (node (ref "J2") (pin "1") (pinfunction "+5V_1") (pintype "bidirectional"))
    )
    (net (code "62") (name "Net-(J2-D+)") (class "Default")
      (node (ref "C6") (pin "1") (pinfunction "1_1") (pintype "bidirectional"))
      (node (ref "J2") (pin "3") (pinfunction "D+_3") (pintype "bidirectional"))
      (node (ref "R2") (pin "1") (pinfunction "1_1") (pintype "passive"))
    )
    (net (code "63") (name "Net-(J2-D-)") (class "Default")
      (node (ref "C5") (pin "1") (pinfunction "1_1") (pintype "bidirectional"))
      (node (ref "J2") (pin "2") (pinfunction "D-_2") (pintype "bidirectional"))
      (node (ref "R1") (pin "1") (pinfunction "1_1") (pintype "passive"))
    )
    (net (code "64") (name "Net-(J3-D+)") (class "Default")
      (node (ref "J3") (pin "3") (pinfunction "D+_3") (pintype "bidirectional"))
      (node (ref "U7") (pin "1") (pinfunction "D1+_1") (pintype "bidirectional"))
    )
    (net (code "65") (name "Net-(J3-D-)") (class "Default")
      (node (ref "J3") (pin "2") (pinfunction "D-_2") (pintype "bidirectional"))
      (node (ref "U7") (pin "7") (pinfunction "D1-_7") (pintype "bidirectional"))
    )
    (net (code "66") (name "Net-(L1-1)") (class "Default")
      (node (ref "L1") (pin "P$1") (pinfunction "1_P$1") (pintype "bidirectional"))
      (node (ref "VR1") (pin "6") (pinfunction "SW_6") (pintype "bidirectional"))
    )
    (net (code "67") (name "Net-(L2-1)") (class "Default")
      (node (ref "C12") (pin "1") (pinfunction "1_1") (pintype "bidirectional"))
      (node (ref "C25") (pin "1") (pinfunction "1_1") (pintype "bidirectional"))
      (node (ref "L2") (pin "P$1") (pinfunction "1_P$1") (pintype "bidirectional"))
      (node (ref "U4") (pin "7") (pinfunction "VDDOUT_7") (pintype "power_in"))
    )
    (net (code "68") (name "Net-(L2-2)") (class "Default")
      (node (ref "L2") (pin "P$2") (pinfunction "2_P$2") (pintype "bidirectional"))
      (node (ref "U4") (pin "5") (pinfunction "VDDCORE_5") (pintype "power_in"))
    )
    (net (code "69") (name "Net-(L3-1)") (class "Default")
      (node (ref "C17") (pin "1") (pinfunction "1_1") (pintype "bidirectional"))
      (node (ref "C26") (pin "1") (pinfunction "1_1") (pintype "bidirectional"))
      (node (ref "L3") (pin "P$1") (pinfunction "1_P$1") (pintype "bidirectional"))
      (node (ref "U5") (pin "7") (pinfunction "VDDOUT_7") (pintype "power_in"))
    )
    (net (code "70") (name "Net-(L3-2)") (class "Default")
      (node (ref "L3") (pin "P$2") (pinfunction "2_P$2") (pintype "bidirectional"))
      (node (ref "U5") (pin "5") (pinfunction "VDDCORE_5") (pintype "power_in"))
    )
    (net (code "71") (name "Net-(SW3-VLOAD)") (class "Default")
      (node (ref "J10") (pin "1") (pinfunction "1_1") (pintype "passive"))
      (node (ref "SW3") (pin "1") (pinfunction "VLOAD_1") (pintype "bidirectional"))
    )
    (net (code "72") (name "Net-(SW4-VLOAD)") (class "Default")
      (node (ref "J11") (pin "1") (pinfunction "1_1") (pintype "passive"))
      (node (ref "SW4") (pin "1") (pinfunction "VLOAD_1") (pintype "bidirectional"))
    )
    (net (code "73") (name "Net-(SW5-VLOAD)") (class "Default")
      (node (ref "J12") (pin "1") (pinfunction "1_1") (pintype "passive"))
      (node (ref "SW5") (pin "1") (pinfunction "VLOAD_1") (pintype "bidirectional"))
    )
    (net (code "74") (name "Net-(U2-RXD)") (class "Default")
      (node (ref "R4") (pin "1") (pinfunction "1_1") (pintype "passive"))
      (node (ref "U2") (pin "10") (pinfunction "RXD_10") (pintype "bidirectional"))
    )
    (net (code "75") (name "Net-(U2-TXD)") (class "Default")
      (node (ref "R3") (pin "1") (pinfunction "1_1") (pintype "passive"))
      (node (ref "U2") (pin "7") (pinfunction "TXD_7") (pintype "bidirectional"))
    )
    (net (code "76") (name "Net-(U2-USBDM)") (class "Default")
      (node (ref "R1") (pin "2") (pinfunction "2_2") (pintype "passive"))
      (node (ref "U2") (pin "1") (pinfunction "USBDM_1") (pintype "bidirectional"))
    )
    (net (code "77") (name "Net-(U2-USBDP)") (class "Default")
      (node (ref "R2") (pin "2") (pinfunction "2_2") (pintype "passive"))
      (node (ref "U2") (pin "12") (pinfunction "USBDP_12") (pintype "bidirectional"))
    )
    (net (code "78") (name "Net-(U2-VCC)") (class "Default")
      (node (ref "C7") (pin "1") (pinfunction "1_1") (pintype "bidirectional"))
      (node (ref "FB2") (pin "P$1") (pinfunction "P$1_P$1") (pintype "bidirectional"))
      (node (ref "U2") (pin "4") (pinfunction "VCC_4") (pintype "bidirectional"))
    )
    (net (code "79") (name "Net-(U3-VBACKUP)") (class "Default")
      (node (ref "C18") (pin "1") (pinfunction "1_1") (pintype "bidirectional"))
      (node (ref "J11") (pin "2") (pinfunction "2_2") (pintype "passive"))
      (node (ref "U3") (pin "11") (pinfunction "VBACKUP_11") (pintype "bidirectional"))
      (node (ref "U3") (pin "12") (pinfunction "VCC_12") (pintype "bidirectional"))
    )
    (net (code "80") (name "Net-(U4-BIASH)") (class "Default")
      (node (ref "U4") (pin "36") (pinfunction "BIASH_36") (pintype "bidirectional"))
      (node (ref "U4") (pin "37") (pinfunction "BIASL_37") (pintype "bidirectional"))
    )
    (net (code "81") (name "Net-(U4-CAPH)") (class "Default")
      (node (ref "U4") (pin "33") (pinfunction "CAPH_33") (pintype "bidirectional"))
      (node (ref "U4") (pin "34") (pinfunction "CAPL_34") (pintype "bidirectional"))
    )
    (net (code "82") (name "Net-(U4-PA02)") (class "Default")
      (node (ref "R11") (pin "1") (pinfunction "1_1") (pintype "passive"))
      (node (ref "R28") (pin "2") (pinfunction "2_2") (pintype "passive"))
      (node (ref "U4") (pin "3") (pinfunction "PA02_3") (pintype "bidirectional"))
    )
    (net (code "83") (name "Net-(U5-BIASH)") (class "Default")
      (node (ref "U5") (pin "36") (pinfunction "BIASH_36") (pintype "bidirectional"))
      (node (ref "U5") (pin "37") (pinfunction "BIASL_37") (pintype "bidirectional"))
    )
    (net (code "84") (name "Net-(U5-CAPH)") (class "Default")
      (node (ref "U5") (pin "33") (pinfunction "CAPH_33") (pintype "bidirectional"))
      (node (ref "U5") (pin "34") (pinfunction "CAPL_34") (pintype "bidirectional"))
    )
    (net (code "85") (name "Net-(U5-PA02)") (class "Default")
      (node (ref "R12") (pin "1") (pinfunction "1_1") (pintype "passive"))
      (node (ref "R27") (pin "2") (pinfunction "2_2") (pintype "passive"))
      (node (ref "U5") (pin "3") (pinfunction "PA02_3") (pintype "bidirectional"))
    )
    (net (code "86") (name "Net-(U7-S)") (class "Default")
      (node (ref "Q1") (pin "D2") (pinfunction "D2_D2") (pintype "bidirectional"))
      (node (ref "R23") (pin "2") (pinfunction "2_2") (pintype "passive"))
      (node (ref "U7") (pin "10") (pinfunction "S_10") (pintype "bidirectional"))
    )
    (net (code "87") (name "Net-(U8-B7)") (class "Default")
      (node (ref "R6") (pin "2") (pinfunction "2_2") (pintype "passive"))
      (node (ref "U8") (pin "13") (pinfunction "B7_13") (pintype "bidirectional"))
    )
    (net (code "88") (name "Net-(U8-B8)") (class "Default")
      (node (ref "R7") (pin "2") (pinfunction "2_2") (pintype "passive"))
      (node (ref "U8") (pin "12") (pinfunction "B8_12") (pintype "bidirectional"))
    )
    (net (code "89") (name "PPS") (class "Default")
      (node (ref "J4") (pin "25") (pinfunction "PPS_25") (pintype "bidirectional"))
      (node (ref "U3") (pin "3") (pinfunction "1PPS_3") (pintype "bidirectional"))
    )
    (net (code "90") (name "SD_ENABLE_POWER") (class "Default")
      (node (ref "R26") (pin "1") (pinfunction "1_1") (pintype "passive"))
      (node (ref "SW5") (pin "4") (pinfunction "EN_4") (pintype "bidirectional"))
      (node (ref "U4") (pin "55") (pinfunction "PA21_55") (pintype "bidirectional"))
    )
    (net (code "91") (name "SD_MISO") (class "Default")
      (node (ref "J1") (pin "7") (pinfunction "DATA0/MISO_7") (pintype "bidirectional"))
      (node (ref "J7") (pin "2") (pinfunction "2_2") (pintype "passive"))
      (node (ref "R15") (pin "1") (pinfunction "1_1") (pintype "passive"))
      (node (ref "U4") (pin "42") (pinfunction "PA15_42") (pintype "bidirectional"))
    )
    (net (code "92") (name "SD_MOSI") (class "Default")
      (node (ref "J1") (pin "3") (pinfunction "CMD/MOSI_3") (pintype "bidirectional"))
      (node (ref "J7") (pin "1") (pinfunction "1_1") (pintype "passive"))
      (node (ref "R13") (pin "1") (pinfunction "1_1") (pintype "passive"))
      (node (ref "U4") (pin "43") (pinfunction "PA16_43") (pintype "bidirectional"))
    )
    (net (code "93") (name "SD_SCLK") (class "Default")
      (node (ref "J1") (pin "5") (pinfunction "CLK_5") (pintype "bidirectional"))
      (node (ref "J7") (pin "3") (pinfunction "3_3") (pintype "passive"))
      (node (ref "U4") (pin "41") (pinfunction "PA14_41") (pintype "bidirectional"))
    )
    (net (code "94") (name "SMBCLK") (class "Default")
      (node (ref "J4") (pin "5") (pinfunction "SMBCLK_5") (pintype "bidirectional"))
      (node (ref "U5") (pin "56") (pinfunction "PA22_56") (pintype "bidirectional"))
    )
    (net (code "95") (name "SMBDATA") (class "Default")
      (node (ref "J4") (pin "3") (pinfunction "SMBDATA_3") (pintype "bidirectional"))
      (node (ref "U5") (pin "55") (pinfunction "PA21_55") (pintype "bidirectional"))
    )
    (net (code "96") (name "STORAGE_DEBUG_GPIO1") (class "Default")
      (node (ref "J4") (pin "201") (pinfunction "DBG_GPIO1_201") (pintype "bidirectional"))
      (node (ref "U4") (pin "19") (pinfunction "PB04_19") (pintype "bidirectional"))
    )
    (net (code "97") (name "STORAGE_DEBUG_GPIO2") (class "Default")
      (node (ref "J4") (pin "204") (pinfunction "DBG_GPIO2_204") (pintype "bidirectional"))
      (node (ref "U4") (pin "20") (pinfunction "PB05_20") (pintype "bidirectional"))
    )
    (net (code "98") (name "STORAGE_DEBUG_RX") (class "Default")
      (node (ref "J4") (pin "203") (pinfunction "DBG_RX_203") (pintype "bidirectional"))
      (node (ref "U4") (pin "46") (pinfunction "PB09_46") (pintype "bidirectional"))
    )
    (net (code "99") (name "STORAGE_DEBUG_TX") (class "Default")
      (node (ref "J4") (pin "202") (pinfunction "DBG_TX_202") (pintype "bidirectional"))
      (node (ref "U4") (pin "47") (pinfunction "PB10_47") (pintype "bidirectional"))
    )
    (net (code "100") (name "STORAGE_SWDCLK") (class "Default")
      (node (ref "J14") (pin "4") (pinfunction "SWDCLK_4") (pintype "bidirectional"))
      (node (ref "J4") (pin "206") (pinfunction "DBG_SWDCLK_206") (pintype "bidirectional"))
      (node (ref "R18") (pin "1") (pinfunction "1_1") (pintype "passive"))
      (node (ref "U4") (pin "9") (pinfunction "TCK_9") (pintype "bidirectional"))
    )
    (net (code "101") (name "STORAGE_SWDIO") (class "Default")
      (node (ref "J14") (pin "2") (pinfunction "SWDIO_2") (pintype "bidirectional"))
      (node (ref "J4") (pin "207") (pinfunction "DBG_SWDIO_207") (pintype "bidirectional"))
      (node (ref "R17") (pin "1") (pinfunction "1_1") (pintype "passive"))
      (node (ref "U4") (pin "10") (pinfunction "PA03_10") (pintype "bidirectional"))
    )
    (net (code "102") (name "STORAGE_XIN") (class "Default")
      (node (ref "C1") (pin "1") (pinfunction "1_1") (pintype "bidirectional"))
      (node (ref "U4") (pin "1") (pinfunction "PA00_1") (pintype "bidirectional"))
      (node (ref "X1") (pin "3") (pinfunction "2_3") (pintype "bidirectional"))
    )
    (net (code "103") (name "STORAGE_XOUT") (class "Default")
      (node (ref "C2") (pin "1") (pinfunction "1_1") (pintype "bidirectional"))
      (node (ref "U4") (pin "2") (pinfunction "PA01_2") (pintype "bidirectional"))
      (node (ref "X1") (pin "1") (pinfunction "1_1") (pintype "bidirectional"))
    )
    (net (code "104") (name "USB_MOD_D+") (class "Default")
      (node (ref "J4") (pin "27") (pinfunction "USB_D+_27") (pintype "bidirectional"))
      (node (ref "U7") (pin "2") (pinfunction "D2+_2") (pintype "bidirectional"))
    )
    (net (code "105") (name "USB_MOD_D-") (class "Default")
      (node (ref "J4") (pin "28") (pinfunction "USB_D-_28") (pintype "bidirectional"))
      (node (ref "U7") (pin "6") (pinfunction "D2-_6") (pintype "bidirectional"))
    )
    (net (code "106") (name "USB_VBUS") (class "Default")
      (node (ref "D1") (pin "ANODE") (pinfunction "ANODE_ANODE") (pintype "bidirectional"))
      (node (ref "E_1") (pin "20") (pinfunction "USB_VBUS_20") (pintype "bidirectional"))
      (node (ref "J3") (pin "1") (pinfunction "+5V_1") (pintype "bidirectional"))
      (node (ref "Q1") (pin "G2") (pinfunction "G2_G2") (pintype "input"))
      (node (ref "R22") (pin "1") (pinfunction "1_1") (pintype "passive"))
      (node (ref "U6") (pin "1") (pinfunction "~{OE}_1") (pintype "bidirectional"))
    )
    (net (code "107") (name "VCC_CONTROLLER") (class "Default")
      (node (ref "C10") (pin "1") (pinfunction "1_1") (pintype "bidirectional"))
      (node (ref "C11") (pin "1") (pinfunction "1_1") (pintype "bidirectional"))
      (node (ref "C14") (pin "1") (pinfunction "1_1") (pintype "bidirectional"))
      (node (ref "C15") (pin "1") (pinfunction "1_1") (pintype "bidirectional"))
      (node (ref "C16") (pin "1") (pinfunction "1_1") (pintype "bidirectional"))
      (node (ref "C19") (pin "1") (pinfunction "1_1") (pintype "bidirectional"))
      (node (ref "C29") (pin "1") (pinfunction "1_1") (pintype "bidirectional"))
      (node (ref "C9") (pin "1") (pinfunction "1_1") (pintype "bidirectional"))
      (node (ref "D3") (pin "1") (pinfunction "VDD_1") (pintype "bidirectional"))
      (node (ref "FB3") (pin "2") (pinfunction "P$2_2") (pintype "bidirectional"))
      (node (ref "FB4") (pin "2") (pinfunction "P$2_2") (pintype "bidirectional"))
      (node (ref "J14") (pin "1") (pinfunction "VCC_1") (pintype "bidirectional"))
      (node (ref "J15") (pin "1") (pinfunction "VCC_1") (pintype "bidirectional"))
      (node (ref "J4") (pin "2") (pinfunction "VCC_CONTROLLER_2") (pintype "bidirectional"))
      (node (ref "J7") (pin "20") (pinfunction "20_20") (pintype "passive"))
      (node (ref "R11") (pin "2") (pinfunction "2_2") (pintype "passive"))
      (node (ref "R12") (pin "2") (pinfunction "2_2") (pintype "passive"))
      (node (ref "R17") (pin "2") (pinfunction "2_2") (pintype "passive"))
      (node (ref "R18") (pin "2") (pinfunction "2_2") (pintype "passive"))
      (node (ref "R19") (pin "2") (pinfunction "2_2") (pintype "passive"))
      (node (ref "R20") (pin "2") (pinfunction "2_2") (pintype "passive"))
      (node (ref "R25") (pin "2") (pinfunction "2_2") (pintype "passive"))
      (node (ref "R26") (pin "2") (pinfunction "2_2") (pintype "passive"))
      (node (ref "SW4") (pin "3") (pinfunction "VSUPP_3") (pintype "bidirectional"))
      (node (ref "SW5") (pin "3") (pinfunction "VSUPP_3") (pintype "bidirectional"))
      (node (ref "U1") (pin "3") (pinfunction "~{WP}_3") (pintype "bidirectional"))
      (node (ref "U1") (pin "7") (pinfunction "~{HOLD}_7") (pintype "bidirectional"))
      (node (ref "U1") (pin "8") (pinfunction "VDD_8") (pintype "bidirectional"))
      (node (ref "U4") (pin "35") (pinfunction "VLCD_35") (pintype "bidirectional"))
      (node (ref "U4") (pin "39") (pinfunction "VLCDIN_39") (pintype "power_in"))
      (node (ref "U4") (pin "52") (pinfunction "VDDIO_52") (pintype "power_in"))
      (node (ref "U4") (pin "61") (pinfunction "VDDIO_61") (pintype "power_in"))
      (node (ref "U4") (pin "8") (pinfunction "VDDIN_8") (pintype "power_in"))
      (node (ref "U5") (pin "35") (pinfunction "VLCD_35") (pintype "bidirectional"))
      (node (ref "U5") (pin "39") (pinfunction "VLCDIN_39") (pintype "power_in"))
      (node (ref "U5") (pin "52") (pinfunction "VDDIO_52") (pintype "power_in"))
      (node (ref "U5") (pin "61") (pinfunction "VDDIO_61") (pintype "power_in"))
      (node (ref "U5") (pin "8") (pinfunction "VDDIN_8") (pintype "power_in"))
    )
    (net (code "108") (name "VCC_LINUX") (class "Default")
      (node (ref "J4") (pin "4") (pinfunction "VCC_LINUX_4") (pintype "bidirectional"))
      (node (ref "J7") (pin "17") (pinfunction "17_17") (pintype "passive"))
      (node (ref "J9") (pin "1") (pinfunction "1_1") (pintype "passive"))
      (node (ref "R24") (pin "2") (pinfunction "2_2") (pintype "passive"))
      (node (ref "SW3") (pin "3") (pinfunction "VSUPP_3") (pintype "bidirectional"))
      (node (ref "U6") (pin "5") (pinfunction "VCC_5") (pintype "power_in"))
    )
    (net (code "109") (name "VCC_LINUX_1V8") (class "Default")
      (node (ref "C23") (pin "1") (pinfunction "1_1") (pintype "bidirectional"))
      (node (ref "C24") (pin "2") (pinfunction "2_2") (pintype "bidirectional"))
      (node (ref "E_1") (pin "12") (pinfunction "1.8V_12") (pintype "bidirectional"))
      (node (ref "J7") (pin "14") (pinfunction "14_14") (pintype "passive"))
      (node (ref "U2") (pin "9") (pinfunction "VCCIO_9") (pintype "bidirectional"))
      (node (ref "U8") (pin "10") (pinfunction "OE_10") (pintype "bidirectional"))
      (node (ref "U8") (pin "2") (pinfunction "VCCA_2") (pintype "bidirectional"))
    )
    (net (code "110") (name "VCC_LINUX_3V3") (class "Default")
      (node (ref "C20") (pin "1") (pinfunction "1_1") (pintype "bidirectional"))
      (node (ref "C21") (pin "2") (pinfunction "2_2") (pintype "bidirectional"))
      (node (ref "C22") (pin "1") (pinfunction "1_1") (pintype "bidirectional"))
      (node (ref "C30") (pin "P$1") (pinfunction "1_P$1") (pintype "bidirectional"))
      (node (ref "D2") (pin "1") (pinfunction "VDD_1") (pintype "bidirectional"))
      (node (ref "E_1") (pin "14") (pinfunction "DCIN_14") (pintype "bidirectional"))
      (node (ref "E_1") (pin "2") (pinfunction "VSYS_2") (pintype "bidirectional"))
      (node (ref "E_1") (pin "4") (pinfunction "VSYS_4") (pintype "bidirectional"))
      (node (ref "E_1") (pin "6") (pinfunction "VSYS_6") (pintype "bidirectional"))
      (node (ref "J7") (pin "18") (pinfunction "18_18") (pintype "passive"))
      (node (ref "L1") (pin "P$2") (pinfunction "2_P$2") (pintype "bidirectional"))
      (node (ref "R16") (pin "2") (pinfunction "2_2") (pintype "passive"))
      (node (ref "R23") (pin "1") (pinfunction "1_1") (pintype "passive"))
      (node (ref "U7") (pin "9") (pinfunction "VCC_9") (pintype "bidirectional"))
      (node (ref "U8") (pin "19") (pinfunction "VCCB_19") (pintype "bidirectional"))
      (node (ref "VR1") (pin "3") (pinfunction "FB_3") (pintype "bidirectional"))
      (node (ref "VR1") (pin "4") (pinfunction "VOS_4") (pintype "bidirectional"))
    )
    (net (code "111") (name "unconnected-(E_1A-3.3V-Pad8)") (class "Default")
      (node (ref "E_1") (pin "8") (pinfunction "3.3V_8") (pintype "bidirectional"))
    )
    (net (code "112") (name "unconnected-(E_1A-3.3V-Pad10)") (class "Default")
      (node (ref "E_1") (pin "10") (pinfunction "3.3V_10") (pintype "bidirectional"))
    )
    (net (code "113") (name "unconnected-(E_1A-FW_RCVR-Pad69)") (class "Default")
      (node (ref "E_1") (pin "69") (pinfunction "FW_RCVR_69") (pintype "bidirectional"))
    )
    (net (code "114") (name "unconnected-(E_1A-MSIC_SLP_CLK-Pad7)") (class "Default")
      (node (ref "E_1") (pin "7") (pinfunction "MSIC_SLP_CLK_7") (pintype "bidirectional"))
    )
    (net (code "115") (name "unconnected-(E_1A-OSC_CLK_OUT_0-Pad67)") (class "Default")
      (node (ref "E_1") (pin "67") (pinfunction "OSC_CLK_OUT_0_67") (pintype "bidirectional"))
    )
    (net (code "116") (name "unconnected-(E_1A-RCVR_MODE-Pad31)") (class "Default")
      (node (ref "E_1") (pin "31") (pinfunction "RCVR_MODE_31") (pintype "bidirectional"))
    )
    (net (code "117") (name "unconnected-(E_1A-RESET_OUT#-Pad36)") (class "Default")
      (node (ref "E_1") (pin "36") (pinfunction "RESET_OUT#_36") (pintype "bidirectional"))
    )
    (net (code "118") (name "unconnected-(E_1A-V_VAT_BKUP-Pad23)") (class "Default")
      (node (ref "E_1") (pin "23") (pinfunction "V_VAT_BKUP_23") (pintype "bidirectional"))
    )
    (net (code "119") (name "unconnected-(E_1B-GP13_PWM1-Pad33)") (class "Default")
      (node (ref "E_1") (pin "33") (pinfunction "GP13_PWM1_33") (pintype "bidirectional"))
    )
    (net (code "120") (name "unconnected-(E_1B-GP14-Pad48)") (class "Default")
      (node (ref "E_1") (pin "48") (pinfunction "GP14_48") (pintype "bidirectional"))
    )
    (net (code "121") (name "unconnected-(E_1B-GP15-Pad42)") (class "Default")
      (node (ref "E_1") (pin "42") (pinfunction "GP15_42") (pintype "bidirectional"))
    )
    (net (code "122") (name "unconnected-(E_1B-GP44-Pad24)") (class "Default")
      (node (ref "E_1") (pin "24") (pinfunction "GP44_24") (pintype "bidirectional"))
    )
    (net (code "123") (name "unconnected-(E_1B-GP45-Pad26)") (class "Default")
      (node (ref "E_1") (pin "26") (pinfunction "GP45_26") (pintype "bidirectional"))
    )
    (net (code "124") (name "unconnected-(E_1B-GP46-Pad28)") (class "Default")
      (node (ref "E_1") (pin "28") (pinfunction "GP46_28") (pintype "bidirectional"))
    )
    (net (code "125") (name "unconnected-(E_1B-GP47-Pad30)") (class "Default")
      (node (ref "E_1") (pin "30") (pinfunction "GP47_30") (pintype "bidirectional"))
    )
    (net (code "126") (name "unconnected-(E_1B-GP48-Pad32)") (class "Default")
      (node (ref "E_1") (pin "32") (pinfunction "GP48_32") (pintype "bidirectional"))
    )
    (net (code "127") (name "unconnected-(E_1B-GP49-Pad34)") (class "Default")
      (node (ref "E_1") (pin "34") (pinfunction "GP49_34") (pintype "bidirectional"))
    )
    (net (code "128") (name "unconnected-(E_1B-GP165-Pad25)") (class "Default")
      (node (ref "E_1") (pin "25") (pinfunction "GP165_25") (pintype "bidirectional"))
    )
    (net (code "129") (name "unconnected-(E_1B-GP183_PWM3-Pad39)") (class "Default")
      (node (ref "E_1") (pin "39") (pinfunction "GP183_PWM3_39") (pintype "bidirectional"))
    )
    (net (code "130") (name "unconnected-(E_1C-GP19_I2C_1_SCL-Pad41)") (class "Default")
      (node (ref "E_1") (pin "41") (pinfunction "GP19_I2C_1_SCL_41") (pintype "bidirectional"))
    )
    (net (code "131") (name "unconnected-(E_1C-GP20_I2C_1_SDA-Pad43)") (class "Default")
      (node (ref "E_1") (pin "43") (pinfunction "GP20_I2C_1_SDA_43") (pintype "bidirectional"))
    )
    (net (code "132") (name "unconnected-(E_1E-GP40_I2S_2_CLK-Pad52)") (class "Default")
      (node (ref "E_1") (pin "52") (pinfunction "GP40_I2S_2_CLK_52") (pintype "bidirectional"))
    )
    (net (code "133") (name "unconnected-(E_1E-GP41_I2S_2_FS-Pad54)") (class "Default")
      (node (ref "E_1") (pin "54") (pinfunction "GP41_I2S_2_FS_54") (pintype "bidirectional"))
    )
    (net (code "134") (name "unconnected-(E_1E-GP42_I2S_2_RXD-Pad50)") (class "Default")
      (node (ref "E_1") (pin "50") (pinfunction "GP42_I2S_2_RXD_50") (pintype "bidirectional"))
    )
    (net (code "135") (name "unconnected-(E_1E-GP43_I2S_2_TXD-Pad56)") (class "Default")
      (node (ref "E_1") (pin "56") (pinfunction "GP43_I2S_2_TXD_56") (pintype "bidirectional"))
    )
    (net (code "136") (name "unconnected-(E_1F-GP77_SD_0_CD#-Pad60)") (class "Default")
      (node (ref "E_1") (pin "60") (pinfunction "GP77_SD_0_CD#_60") (pintype "bidirectional"))
    )
    (net (code "137") (name "unconnected-(E_1F-GP78_SD_0_CLK-Pad58)") (class "Default")
      (node (ref "E_1") (pin "58") (pinfunction "GP78_SD_0_CLK_58") (pintype "bidirectional"))
    )
    (net (code "138") (name "unconnected-(E_1F-GP79_SD_0_CMD-Pad62)") (class "Default")
      (node (ref "E_1") (pin "62") (pinfunction "GP79_SD_0_CMD_62") (pintype "bidirectional"))
    )
    (net (code "139") (name "unconnected-(E_1F-GP80_SD_0_DAT0-Pad66)") (class "Default")
      (node (ref "E_1") (pin "66") (pinfunction "GP80_SD_0_DAT0_66") (pintype "bidirectional"))
    )
    (net (code "140") (name "unconnected-(E_1F-GP81_SD_0_DAT1-Pad70)") (class "Default")
      (node (ref "E_1") (pin "70") (pinfunction "GP81_SD_0_DAT1_70") (pintype "bidirectional"))
    )
    (net (code "141") (name "unconnected-(E_1F-GP82_SD_0_DAT2-Pad64)") (class "Default")
      (node (ref "E_1") (pin "64") (pinfunction "GP82_SD_0_DAT2_64") (pintype "bidirectional"))
    )
    (net (code "142") (name "unconnected-(E_1F-GP83_SD_0_DAT3-Pad68)") (class "Default")
      (node (ref "E_1") (pin "68") (pinfunction "GP83_SD_0_DAT3_68") (pintype "bidirectional"))
    )
    (net (code "143") (name "unconnected-(E_1F-GP84_SD_0_CLK_FB-Pad44)") (class "Default")
      (node (ref "E_1") (pin "44") (pinfunction "GP84_SD_0_CLK_FB_44") (pintype "bidirectional"))
    )
    (net (code "144") (name "unconnected-(E_1H-GP128_UART_1_CTS-Pad65)") (class "Default")
      (node (ref "E_1") (pin "65") (pinfunction "GP128_UART_1_CTS_65") (pintype "bidirectional"))
    )
    (net (code "145") (name "unconnected-(E_1H-GP129_UART_1_RTS-Pad63)") (class "Default")
      (node (ref "E_1") (pin "63") (pinfunction "GP129_UART_1_RTS_63") (pintype "bidirectional"))
    )
    (net (code "146") (name "unconnected-(E_1H-GP130_UART_1_RX-Pad61)") (class "Default")
      (node (ref "E_1") (pin "61") (pinfunction "GP130_UART_1_RX_61") (pintype "bidirectional"))
    )
    (net (code "147") (name "unconnected-(E_1H-GP131_UART_1_TX-Pad46)") (class "Default")
      (node (ref "E_1") (pin "46") (pinfunction "GP131_UART_1_TX_46") (pintype "bidirectional"))
    )
    (net (code "148") (name "unconnected-(E_1J-FAULT-Pad19)") (class "Default")
      (node (ref "E_1") (pin "19") (pinfunction "FAULT_19") (pintype "bidirectional"))
    )
    (net (code "149") (name "unconnected-(E_1J-PSW-Pad21)") (class "Default")
      (node (ref "E_1") (pin "21") (pinfunction "PSW_21") (pintype "bidirectional"))
    )
    (net (code "150") (name "unconnected-(J1-DATA1{slash}RSV-Pad8)") (class "Default")
      (node (ref "J1") (pin "8") (pinfunction "DATA1/RSV_8") (pintype "bidirectional"))
    )
    (net (code "151") (name "unconnected-(J1-DATA2{slash}NC-Pad1)") (class "Default")
      (node (ref "J1") (pin "1") (pinfunction "DATA2/NC_1") (pintype "bidirectional"))
    )
    (net (code "152") (name "unconnected-(J2-ID-Pad4)") (class "Default")
      (node (ref "J2") (pin "4") (pinfunction "ID_4") (pintype "bidirectional"))
    )
    (net (code "153") (name "unconnected-(J3-ID-Pad4)") (class "Default")
      (node (ref "J3") (pin "4") (pinfunction "ID_4") (pintype "bidirectional"))
    )
    (net (code "154") (name "unconnected-(J14-SWO-Pad6)") (class "Default")
      (node (ref "J14") (pin "6") (pinfunction "SWO_6") (pintype "bidirectional"))
    )
    (net (code "155") (name "unconnected-(J15-SWO-Pad6)") (class "Default")
      (node (ref "J15") (pin "6") (pinfunction "SWO_6") (pintype "bidirectional"))
    )
    (net (code "156") (name "unconnected-(Q1-PadD1)") (class "Default")
      (node (ref "Q1") (pin "D1") (pinfunction "D1_D1") (pintype "bidirectional"))
    )
    (net (code "157") (name "unconnected-(Q1-PadG1)") (class "Default")
      (node (ref "Q1") (pin "G1") (pinfunction "G1_G1") (pintype "input"))
    )
    (net (code "158") (name "unconnected-(U2-3V3OUT-Pad3)") (class "Default")
      (node (ref "U2") (pin "3") (pinfunction "3V3OUT_3") (pintype "bidirectional"))
    )
    (net (code "159") (name "unconnected-(U2-CBUS0-Pad6)") (class "Default")
      (node (ref "U2") (pin "6") (pinfunction "CBUS0_6") (pintype "bidirectional"))
    )
    (net (code "160") (name "unconnected-(U2-~{CTS}-Pad11)") (class "Default")
      (node (ref "U2") (pin "11") (pinfunction "~{CTS}_11") (pintype "bidirectional"))
    )
    (net (code "161") (name "unconnected-(U2-~{RESET}-Pad2)") (class "Default")
      (node (ref "U2") (pin "2") (pinfunction "~{RESET}_2") (pintype "bidirectional"))
    )
    (net (code "162") (name "unconnected-(U2-~{RTS}-Pad8)") (class "Default")
      (node (ref "U2") (pin "8") (pinfunction "~{RTS}_8") (pintype "bidirectional"))
    )
    (net (code "163") (name "unconnected-(U3-~{RESET}-Pad8)") (class "Default")
      (node (ref "U3") (pin "8") (pinfunction "~{RESET}_8") (pintype "bidirectional"))
    )
    (net (code "164") (name "unconnected-(U4-ADVREFP-Pad24)") (class "Default")
      (node (ref "U4") (pin "24") (pinfunction "ADVREFP_24") (pintype "bidirectional"))
    )
    (net (code "165") (name "unconnected-(U4-PA04-Pad15)") (class "Default")
      (node (ref "U4") (pin "15") (pinfunction "PA04_15") (pintype "bidirectional"))
    )
    (net (code "166") (name "unconnected-(U4-PA08-Pad26)") (class "Default")
      (node (ref "U4") (pin "26") (pinfunction "PA08_26") (pintype "bidirectional"))
    )
    (net (code "167") (name "unconnected-(U4-PA25-Pad62)") (class "Default")
      (node (ref "U4") (pin "62") (pinfunction "PA25_62") (pintype "bidirectional"))
    )
    (net (code "168") (name "unconnected-(U4-PA26-Pad63)") (class "Default")
      (node (ref "U4") (pin "63") (pinfunction "PA26_63") (pintype "bidirectional"))
    )
    (net (code "169") (name "unconnected-(U4-PB00-Pad11)") (class "Default")
      (node (ref "U4") (pin "11") (pinfunction "PB00_11") (pintype "bidirectional"))
    )
    (net (code "170") (name "unconnected-(U4-PB01-Pad12)") (class "Default")
      (node (ref "U4") (pin "12") (pinfunction "PB01_12") (pintype "bidirectional"))
    )
    (net (code "171") (name "unconnected-(U4-PB02-Pad13)") (class "Default")
      (node (ref "U4") (pin "13") (pinfunction "PB02_13") (pintype "bidirectional"))
    )
    (net (code "172") (name "unconnected-(U4-PB03-Pad14)") (class "Default")
      (node (ref "U4") (pin "14") (pinfunction "PB03_14") (pintype "bidirectional"))
    )
    (net (code "173") (name "unconnected-(U4-PB06-Pad27)") (class "Default")
      (node (ref "U4") (pin "27") (pinfunction "PB06_27") (pintype "bidirectional"))
    )
    (net (code "174") (name "unconnected-(U4-PB07-Pad28)") (class "Default")
      (node (ref "U4") (pin "28") (pinfunction "PB07_28") (pintype "bidirectional"))
    )
    (net (code "175") (name "unconnected-(U4-PB08-Pad45)") (class "Default")
      (node (ref "U4") (pin "45") (pinfunction "PB08_45") (pintype "bidirectional"))
    )
    (net (code "176") (name "unconnected-(U4-PB11-Pad48)") (class "Default")
      (node (ref "U4") (pin "48") (pinfunction "PB11_48") (pintype "bidirectional"))
    )
    (net (code "177") (name "unconnected-(U4-PB12-Pad53)") (class "Default")
      (node (ref "U4") (pin "53") (pinfunction "PB12_53") (pintype "bidirectional"))
    )
    (net (code "178") (name "unconnected-(U4-PB13-Pad54)") (class "Default")
      (node (ref "U4") (pin "54") (pinfunction "PB13_54") (pintype "bidirectional"))
    )
    (net (code "179") (name "unconnected-(U4-PB14-Pad57)") (class "Default")
      (node (ref "U4") (pin "57") (pinfunction "PB14_57") (pintype "bidirectional"))
    )
    (net (code "180") (name "unconnected-(U4-PB15-Pad58)") (class "Default")
      (node (ref "U4") (pin "58") (pinfunction "PB15_58") (pintype "bidirectional"))
    )
    (net (code "181") (name "unconnected-(U4-XIN32-Pad17)") (class "Default")
      (node (ref "U4") (pin "17") (pinfunction "XIN32_17") (pintype "bidirectional"))
    )
    (net (code "182") (name "unconnected-(U4-XOUT32-Pad18)") (class "Default")
      (node (ref "U4") (pin "18") (pinfunction "XOUT32_18") (pintype "bidirectional"))
    )
    (net (code "183") (name "unconnected-(U5-ADVREFP-Pad24)") (class "Default")
      (node (ref "U5") (pin "24") (pinfunction "ADVREFP_24") (pintype "bidirectional"))
    )
    (net (code "184") (name "unconnected-(U5-PB00-Pad11)") (class "Default")
      (node (ref "U5") (pin "11") (pinfunction "PB00_11") (pintype "bidirectional"))
    )
    (net (code "185") (name "unconnected-(U5-PB01-Pad12)") (class "Default")
      (node (ref "U5") (pin "12") (pinfunction "PB01_12") (pintype "bidirectional"))
    )
    (net (code "186") (name "unconnected-(U5-PB02-Pad13)") (class "Default")
      (node (ref "U5") (pin "13") (pinfunction "PB02_13") (pintype "bidirectional"))
    )
    (net (code "187") (name "unconnected-(U5-PB03-Pad14)") (class "Default")
      (node (ref "U5") (pin "14") (pinfunction "PB03_14") (pintype "bidirectional"))
    )
    (net (code "188") (name "unconnected-(U5-PB06-Pad27)") (class "Default")
      (node (ref "U5") (pin "27") (pinfunction "PB06_27") (pintype "bidirectional"))
    )
    (net (code "189") (name "unconnected-(U5-PB08-Pad45)") (class "Default")
      (node (ref "U5") (pin "45") (pinfunction "PB08_45") (pintype "bidirectional"))
    )
    (net (code "190") (name "unconnected-(U5-PB09-Pad46)") (class "Default")
      (node (ref "U5") (pin "46") (pinfunction "PB09_46") (pintype "bidirectional"))
    )
    (net (code "191") (name "unconnected-(U5-PB10-Pad47)") (class "Default")
      (node (ref "U5") (pin "47") (pinfunction "PB10_47") (pintype "bidirectional"))
    )
    (net (code "192") (name "unconnected-(U5-PB12-Pad53)") (class "Default")
      (node (ref "U5") (pin "53") (pinfunction "PB12_53") (pintype "bidirectional"))
    )
    (net (code "193") (name "unconnected-(U5-XIN32-Pad17)") (class "Default")
      (node (ref "U5") (pin "17") (pinfunction "XIN32_17") (pintype "bidirectional"))
    )
    (net (code "194") (name "unconnected-(U5-XOUT32-Pad18)") (class "Default")
      (node (ref "U5") (pin "18") (pinfunction "XOUT32_18") (pintype "bidirectional"))
    )
    (net (code "195") (name "unconnected-(VR1-PG-Pad2)") (class "Default")
      (node (ref "VR1") (pin "2") (pinfunction "PG_2") (pintype "bidirectional"))
    )
    (net (code "196") (name "~{BACKPLANE_RESET}") (class "Default")
      (node (ref "J4") (pin "22") (pinfunction "~{BACKPLANE_RESET}_22") (pintype "bidirectional"))
      (node (ref "SW2") (pin "1") (pinfunction "P$1_1") (pintype "passive"))
      (node (ref "SW2") (pin "2") (pinfunction "P$1_2") (pintype "passive"))
    )
    (net (code "197") (name "~{CONTROLLER_LED}") (class "Default")
      (node (ref "R10") (pin "2") (pinfunction "2_2") (pintype "passive"))
      (node (ref "U5") (pin "48") (pinfunction "PB11_48") (pintype "bidirectional"))
    )
    (net (code "198") (name "~{CONTROLLER_RESET}") (class "Default")
      (node (ref "J15") (pin "3") (pinfunction "~{RESET}_3") (pintype "bidirectional"))
      (node (ref "J4") (pin "105") (pinfunction "DBG_~{RESET}_105") (pintype "bidirectional"))
      (node (ref "U5") (pin "4") (pinfunction "~{RESET}_4") (pintype "bidirectional"))
    )
    (net (code "199") (name "~{EDISON_PWRBTN}") (class "Default")
      (node (ref "E_1") (pin "17") (pinfunction "PWRBTN#_17") (pintype "bidirectional"))
      (node (ref "J8") (pin "2") (pinfunction "2_2") (pintype "passive"))
      (node (ref "R16") (pin "1") (pinfunction "1_1") (pintype "passive"))
      (node (ref "SW1") (pin "1") (pinfunction "P$1_1") (pintype "passive"))
      (node (ref "U4") (pin "16") (pinfunction "PA05_16") (pintype "bidirectional"))
    )
    (net (code "200") (name "~{EDISON_SPI_CS_1V8}") (class "Default")
      (node (ref "J13") (pin "2") (pinfunction "2_2") (pintype "passive"))
      (node (ref "J7") (pin "13") (pinfunction "13_13") (pintype "passive"))
      (node (ref "U8") (pin "5") (pinfunction "A4_5") (pintype "bidirectional"))
    )
    (net (code "201") (name "~{EDISON_SPI_CS}") (class "Default")
      (node (ref "U4") (pin "56") (pinfunction "PA22_56") (pintype "bidirectional"))
      (node (ref "U8") (pin "16") (pinfunction "B4_16") (pintype "bidirectional"))
    )
    (net (code "202") (name "~{FRAM_CS}") (class "Default")
      (node (ref "J7") (pin "9") (pinfunction "9_9") (pintype "passive"))
      (node (ref "U1") (pin "1") (pinfunction "~{CS}_1") (pintype "bidirectional"))
      (node (ref "U5") (pin "62") (pinfunction "PA25_62") (pintype "bidirectional"))
    )
    (net (code "203") (name "~{SD_CS}") (class "Default")
      (node (ref "J1") (pin "2") (pinfunction "DATA3-CD/CS_N_2") (pintype "bidirectional"))
      (node (ref "J7") (pin "4") (pinfunction "4_4") (pintype "passive"))
      (node (ref "R14") (pin "1") (pinfunction "1_1") (pintype "passive"))
      (node (ref "U4") (pin "40") (pinfunction "PA13_40") (pintype "bidirectional"))
    )
    (net (code "204") (name "~{SD_DETECT}") (class "Default")
      (node (ref "J1") (pin "A") (pinfunction "A_A") (pintype "bidirectional"))
      (node (ref "R21") (pin "1") (pinfunction "1_1") (pintype "passive"))
      (node (ref "U4") (pin "44") (pinfunction "PA17_44") (pintype "bidirectional"))
    )
    (net (code "205") (name "~{SMBALERT}") (class "Default")
      (node (ref "J4") (pin "6") (pinfunction "~{SMBALERT}_6") (pintype "bidirectional"))
      (node (ref "U5") (pin "63") (pinfunction "PA26_63") (pintype "bidirectional"))
    )
    (net (code "206") (name "~{STORAGE_CS}") (class "Default")
      (node (ref "J7") (pin "8") (pinfunction "8_8") (pintype "passive"))
      (node (ref "U4") (pin "29") (pinfunction "PA09_29") (pintype "bidirectional"))
      (node (ref "U5") (pin "54") (pinfunction "PB13_54") (pintype "bidirectional"))
    )
    (net (code "207") (name "~{STORAGE_LED}") (class "Default")
      (node (ref "R9") (pin "2") (pinfunction "2_2") (pintype "passive"))
      (node (ref "U4") (pin "22") (pinfunction "PA07_22") (pintype "bidirectional"))
    )
    (net (code "208") (name "~{STORAGE_RESET}") (class "Default")
      (node (ref "J14") (pin "3") (pinfunction "~{RESET}_3") (pintype "bidirectional"))
      (node (ref "J4") (pin "205") (pinfunction "DBG_~{RESET}_205") (pintype "bidirectional"))
      (node (ref "U4") (pin "4") (pinfunction "~{RESET}_4") (pintype "bidirectional"))
    )
  )
)
